# Filter_Board_rev2.net
KiCad netlist of a schematic drawn in EAGLE
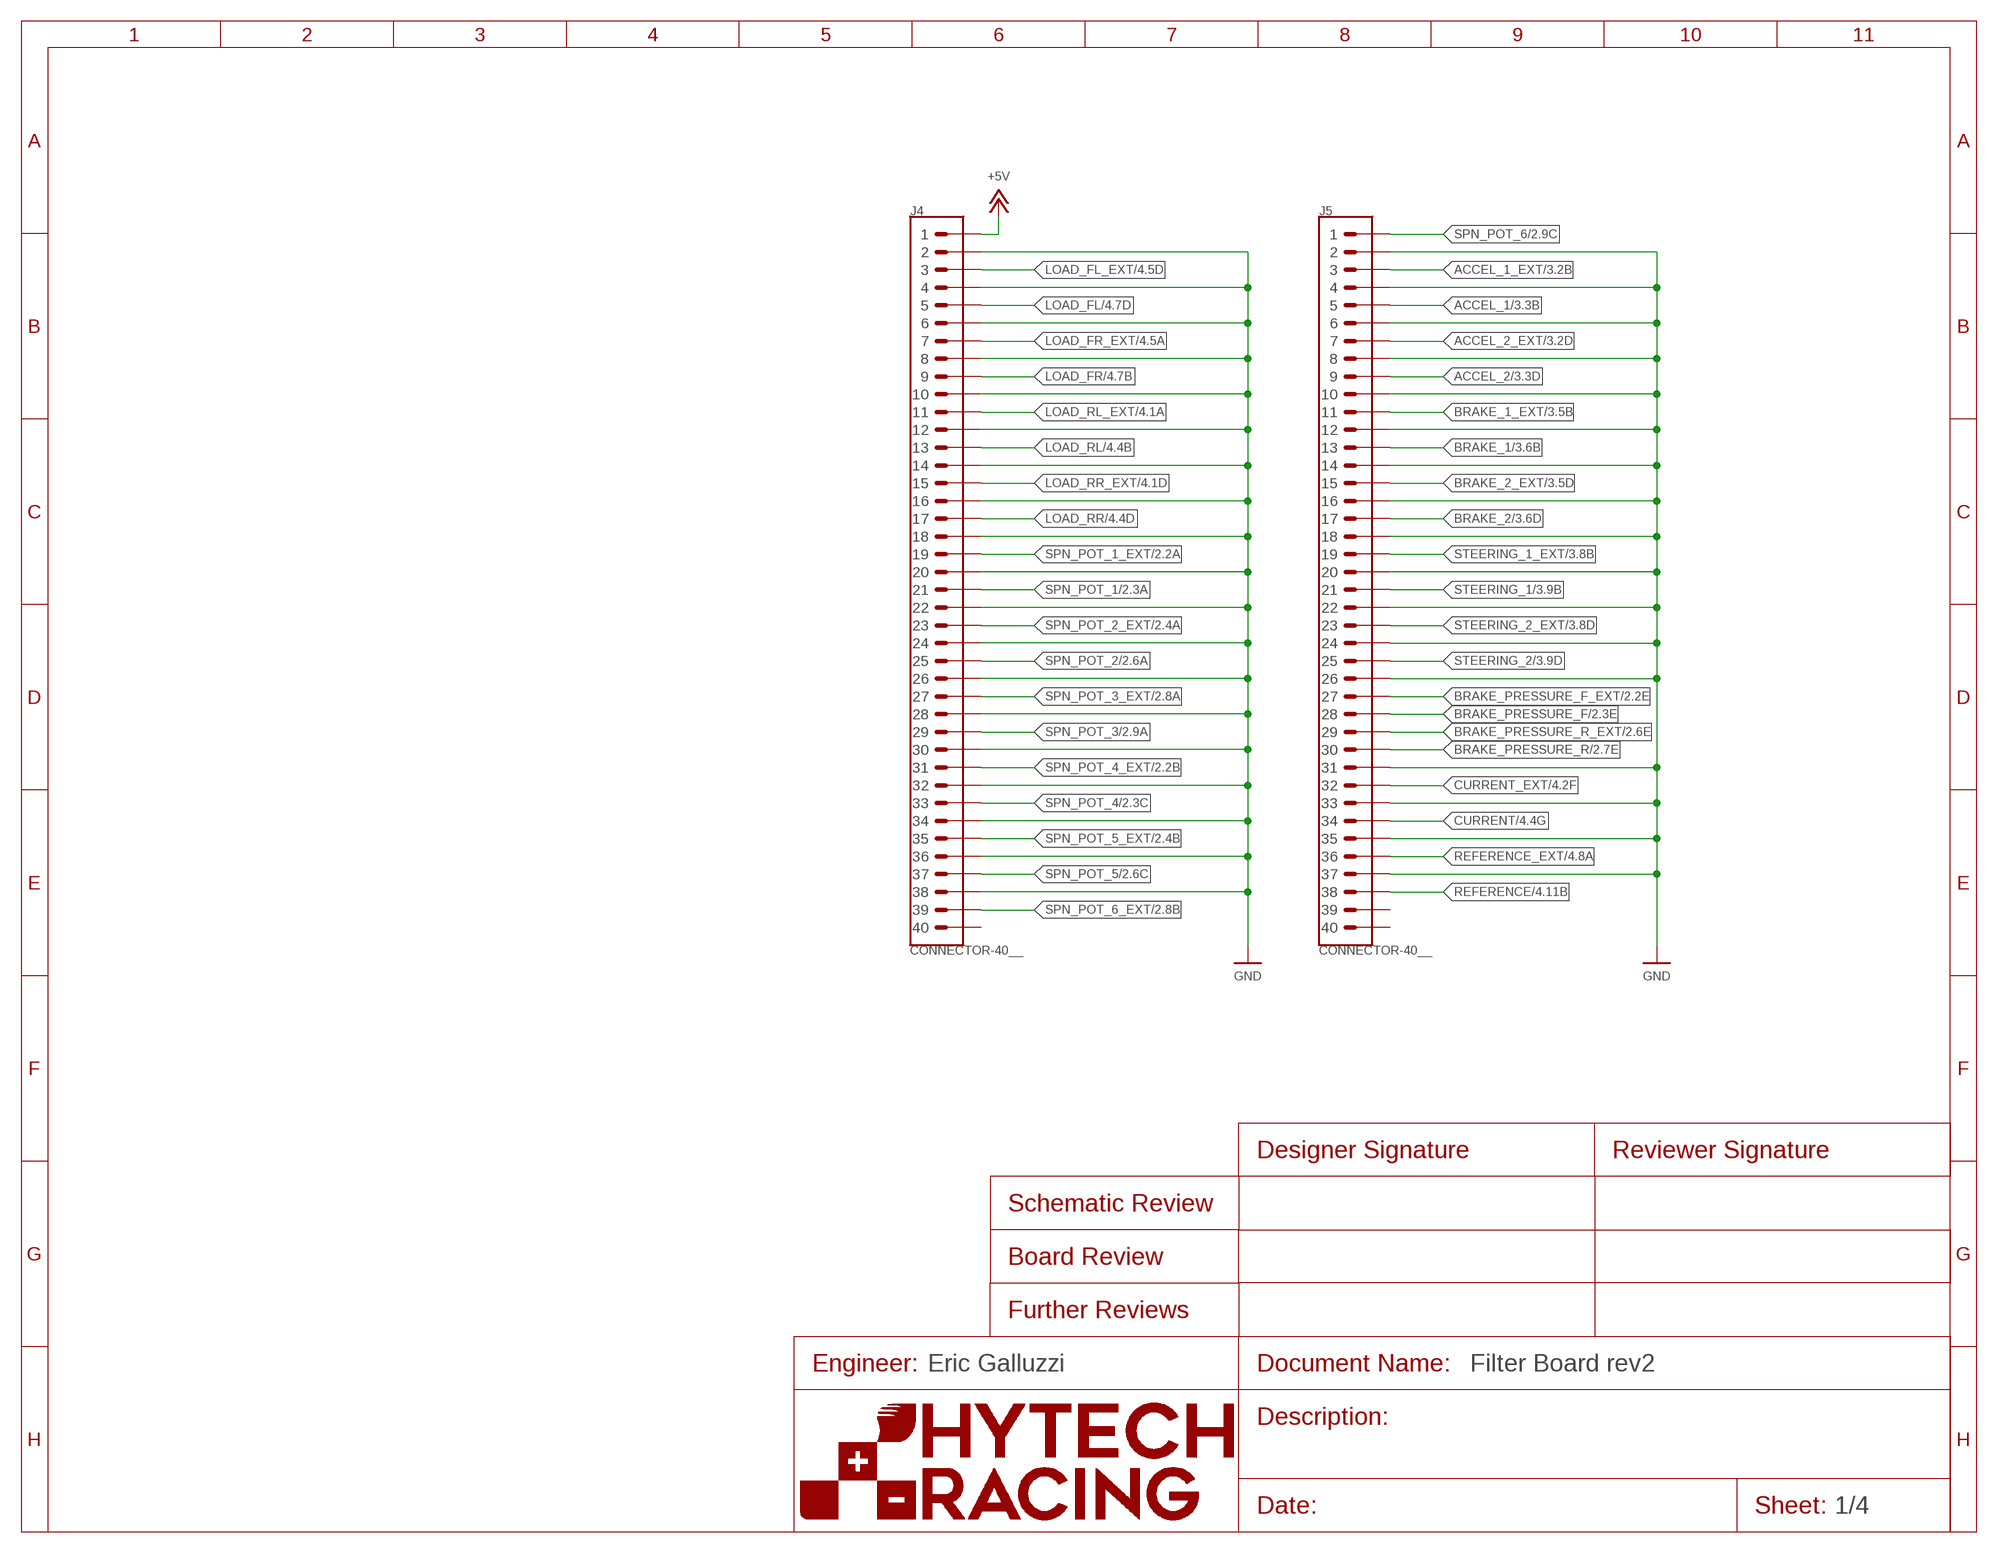
[diagram p0: schematic, sheet 1]
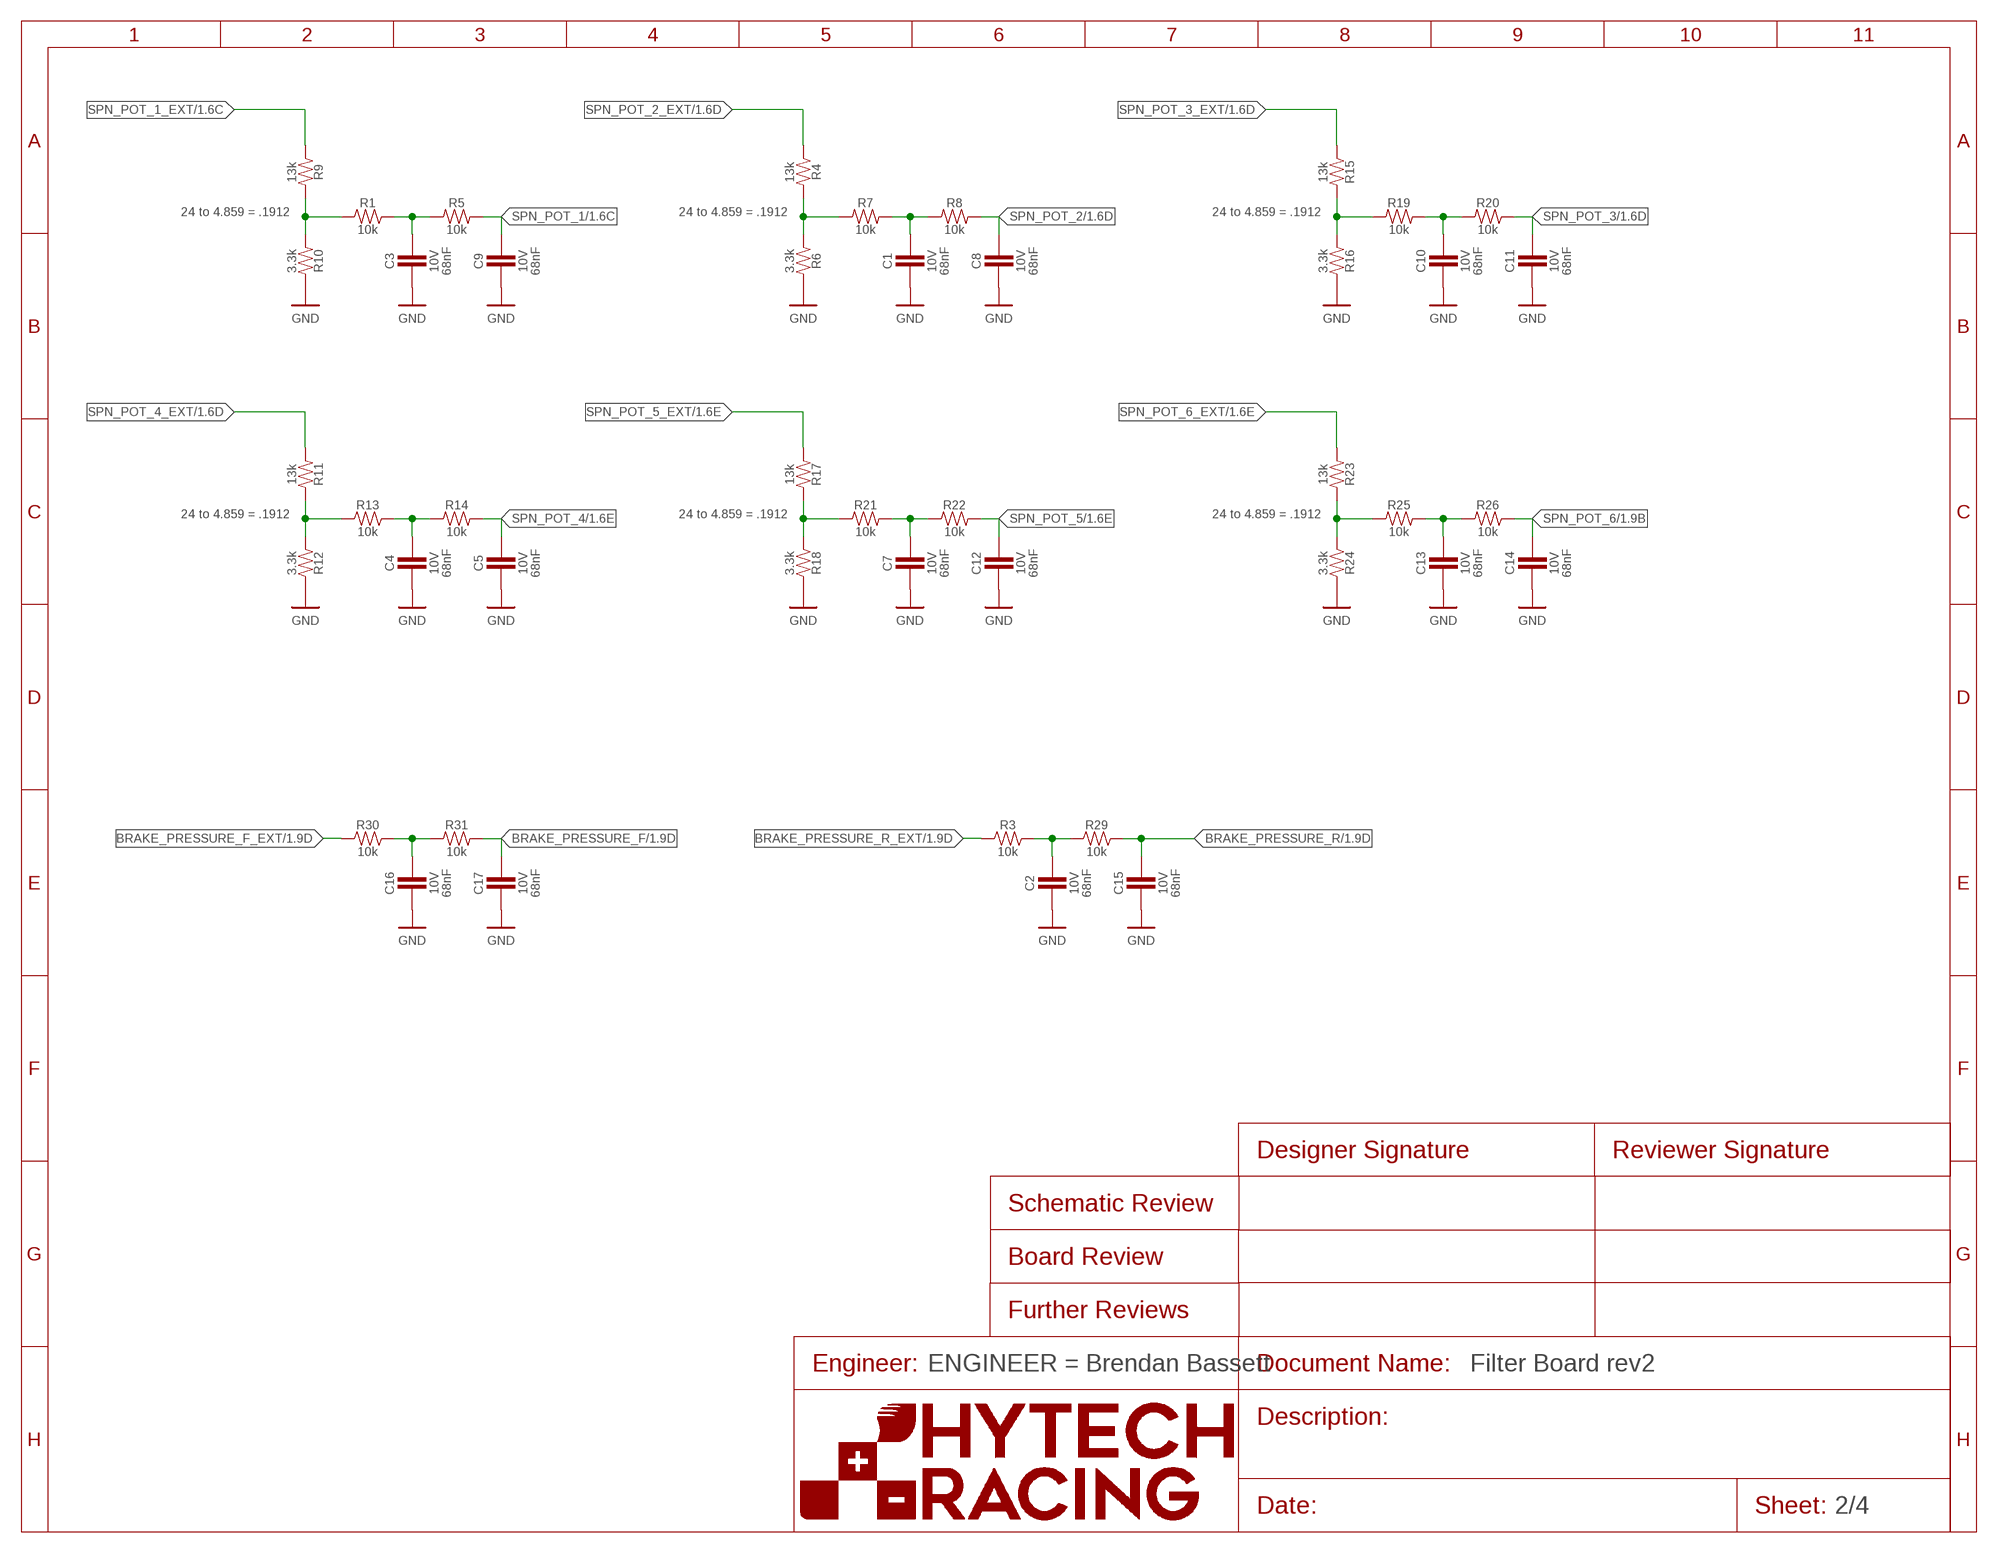
[diagram p1: schematic, sheet 2]
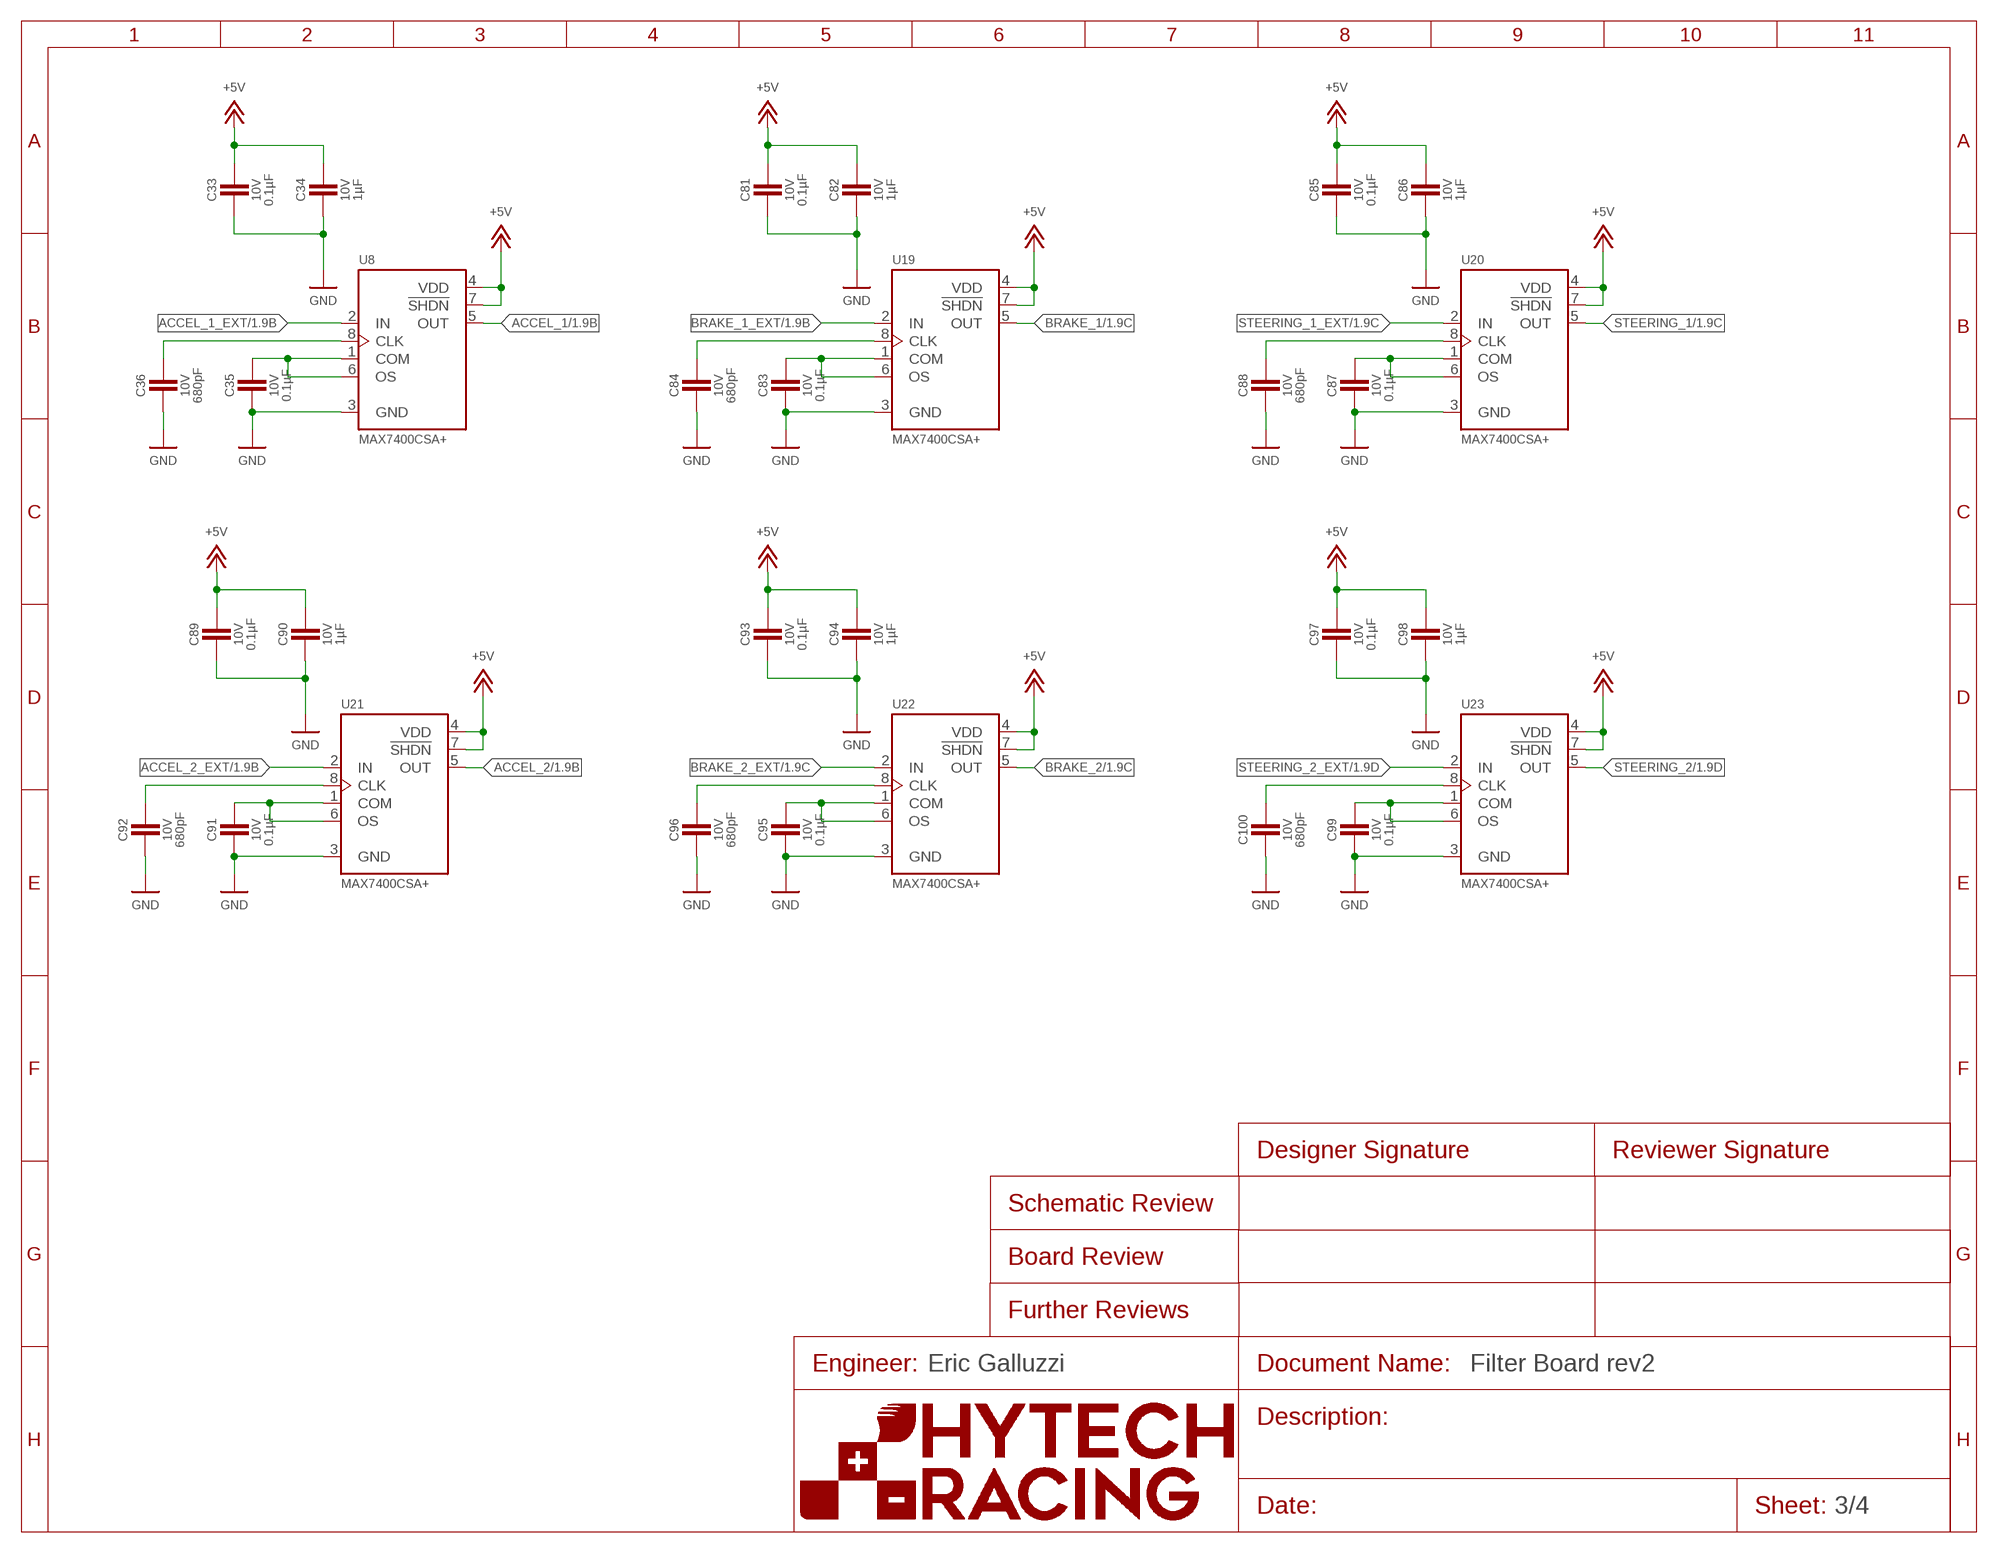
[diagram p2: schematic, sheet 3]
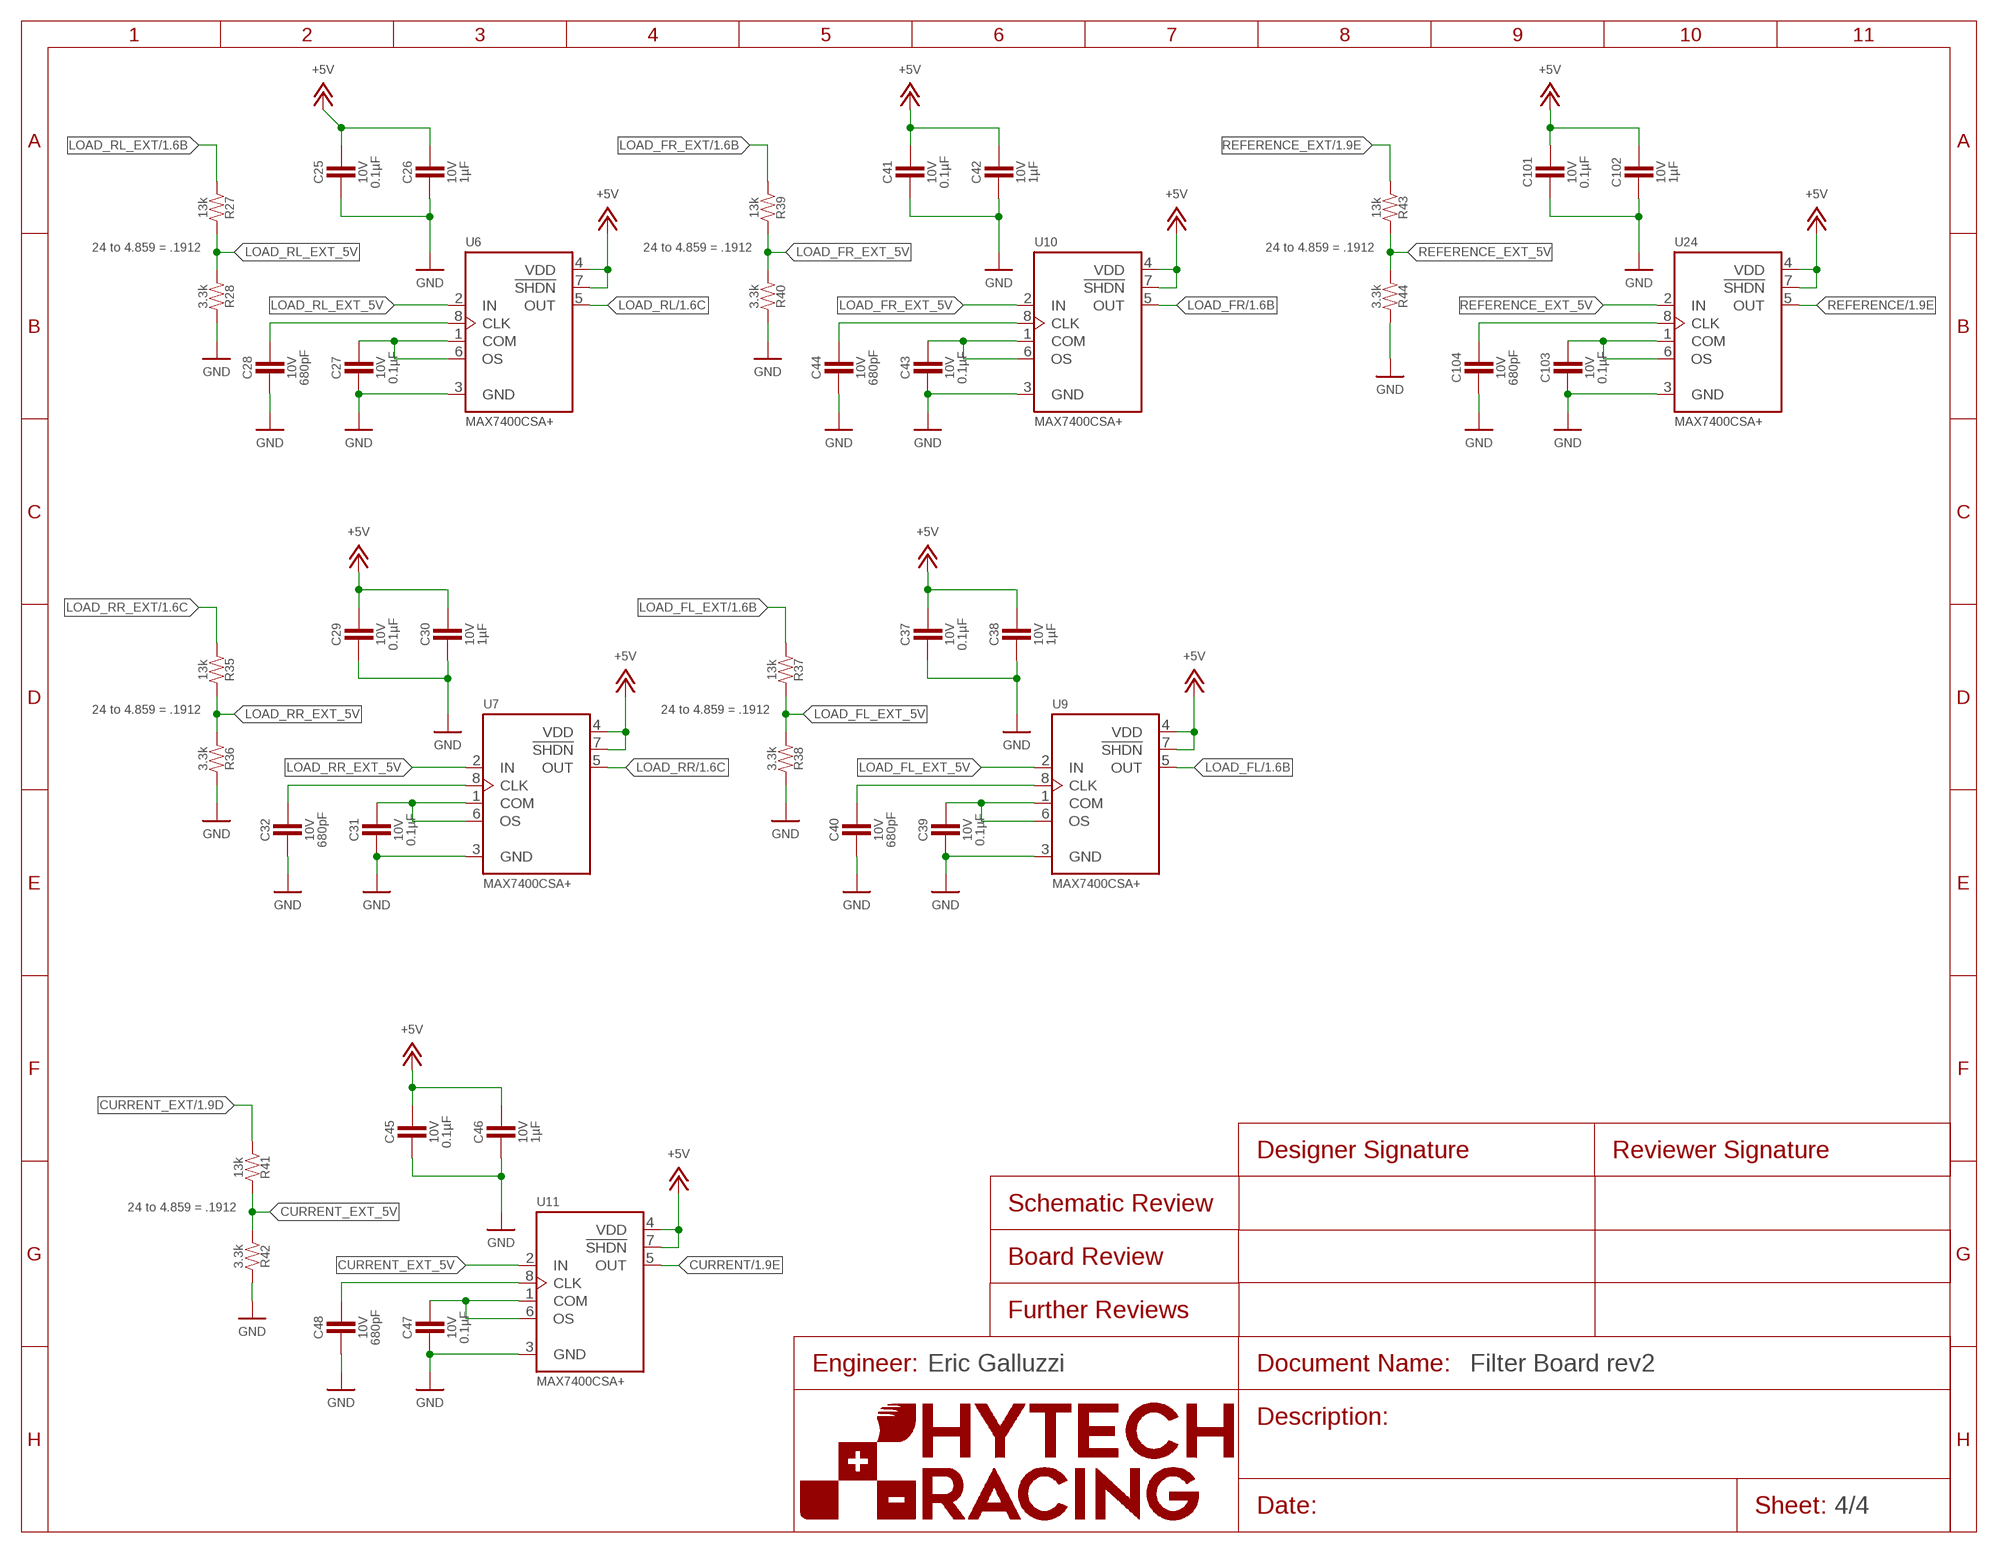
[diagram p3: schematic, sheet 4]

(export (version "E")
  (design (tool "Eeschema 10.0.6"))
  (components
    (comp (ref "C33")
      (value "CAPACITOR_0603_10V_0.1UF")
      (footprint "eagle-import:0603-CAP")
      (fields
        (field (name "CAPACITANCE") "0.1µF")
        (field (name "MANUFACTURER") "Vishay Vitramon")
        (field (name "MPN") "VJ0603Y104JXQPW1BC")
        (field (name "TOLERANCE") "5%")
        (field (name "VOLTAGE") "10V")
      )
      (libsource (lib "eagle-import") (part "CAPACITOR_?_060310V_0.1UF"))
    )
    (comp (ref "C34")
      (value "CAPACITOR_0603_10V_1UF")
      (footprint "eagle-import:0603-CAP")
      (fields
        (field (name "CAPACITANCE") "1µF")
        (field (name "MANUFACTURER") "Yageo")
        (field (name "MPN") "CC0603KRX7R6BB105")
        (field (name "TOLERANCE") "10%")
        (field (name "VOLTAGE") "10V")
      )
      (libsource (lib "eagle-import") (part "CAPACITOR_?_060310V_1UF"))
    )
    (comp (ref "C35")
      (value "CAPACITOR_0603_10V_0.1UF")
      (footprint "eagle-import:0603-CAP")
      (fields
        (field (name "CAPACITANCE") "0.1µF")
        (field (name "MANUFACTURER") "Vishay Vitramon")
        (field (name "MPN") "VJ0603Y104JXQPW1BC")
        (field (name "TOLERANCE") "5%")
        (field (name "VOLTAGE") "10V")
      )
      (libsource (lib "eagle-import") (part "CAPACITOR_?_060310V_0.1UF"))
    )
    (comp (ref "C36")
      (value "CAPACITOR_0603_10V_680PF")
      (footprint "eagle-import:0603-CAP")
      (fields
        (field (name "CAPACITANCE") "680pF")
        (field (name "MANUFACTURER") "Würth Elektronik")
        (field (name "MPN") "885012006013")
        (field (name "TOLERANCE") "5%")
        (field (name "VOLTAGE") "10V")
      )
      (libsource (lib "eagle-import") (part "CAPACITOR_?_060310V_680PF"))
    )
    (comp (ref "C81")
      (value "CAPACITOR_0603_10V_0.1UF")
      (footprint "eagle-import:0603-CAP")
      (fields
        (field (name "CAPACITANCE") "0.1µF")
        (field (name "MANUFACTURER") "Vishay Vitramon")
        (field (name "MPN") "VJ0603Y104JXQPW1BC")
        (field (name "TOLERANCE") "5%")
        (field (name "VOLTAGE") "10V")
      )
      (libsource (lib "eagle-import") (part "CAPACITOR_?_060310V_0.1UF"))
    )
    (comp (ref "C82")
      (value "CAPACITOR_0603_10V_1UF")
      (footprint "eagle-import:0603-CAP")
      (fields
        (field (name "CAPACITANCE") "1µF")
        (field (name "MANUFACTURER") "Yageo")
        (field (name "MPN") "CC0603KRX7R6BB105")
        (field (name "TOLERANCE") "10%")
        (field (name "VOLTAGE") "10V")
      )
      (libsource (lib "eagle-import") (part "CAPACITOR_?_060310V_1UF"))
    )
    (comp (ref "C83")
      (value "CAPACITOR_0603_10V_0.1UF")
      (footprint "eagle-import:0603-CAP")
      (fields
        (field (name "CAPACITANCE") "0.1µF")
        (field (name "MANUFACTURER") "Vishay Vitramon")
        (field (name "MPN") "VJ0603Y104JXQPW1BC")
        (field (name "TOLERANCE") "5%")
        (field (name "VOLTAGE") "10V")
      )
      (libsource (lib "eagle-import") (part "CAPACITOR_?_060310V_0.1UF"))
    )
    (comp (ref "C84")
      (value "CAPACITOR_0603_10V_680PF")
      (footprint "eagle-import:0603-CAP")
      (fields
        (field (name "CAPACITANCE") "680pF")
        (field (name "MANUFACTURER") "Würth Elektronik")
        (field (name "MPN") "885012006013")
        (field (name "TOLERANCE") "5%")
        (field (name "VOLTAGE") "10V")
      )
      (libsource (lib "eagle-import") (part "CAPACITOR_?_060310V_680PF"))
    )
    (comp (ref "C85")
      (value "CAPACITOR_0603_10V_0.1UF")
      (footprint "eagle-import:0603-CAP")
      (fields
        (field (name "CAPACITANCE") "0.1µF")
        (field (name "MANUFACTURER") "Vishay Vitramon")
        (field (name "MPN") "VJ0603Y104JXQPW1BC")
        (field (name "TOLERANCE") "5%")
        (field (name "VOLTAGE") "10V")
      )
      (libsource (lib "eagle-import") (part "CAPACITOR_?_060310V_0.1UF"))
    )
    (comp (ref "C86")
      (value "CAPACITOR_0603_10V_1UF")
      (footprint "eagle-import:0603-CAP")
      (fields
        (field (name "CAPACITANCE") "1µF")
        (field (name "MANUFACTURER") "Yageo")
        (field (name "MPN") "CC0603KRX7R6BB105")
        (field (name "TOLERANCE") "10%")
        (field (name "VOLTAGE") "10V")
      )
      (libsource (lib "eagle-import") (part "CAPACITOR_?_060310V_1UF"))
    )
    (comp (ref "C87")
      (value "CAPACITOR_0603_10V_0.1UF")
      (footprint "eagle-import:0603-CAP")
      (fields
        (field (name "CAPACITANCE") "0.1µF")
        (field (name "MANUFACTURER") "Vishay Vitramon")
        (field (name "MPN") "VJ0603Y104JXQPW1BC")
        (field (name "TOLERANCE") "5%")
        (field (name "VOLTAGE") "10V")
      )
      (libsource (lib "eagle-import") (part "CAPACITOR_?_060310V_0.1UF"))
    )
    (comp (ref "C88")
      (value "CAPACITOR_0603_10V_680PF")
      (footprint "eagle-import:0603-CAP")
      (fields
        (field (name "CAPACITANCE") "680pF")
        (field (name "MANUFACTURER") "Würth Elektronik")
        (field (name "MPN") "885012006013")
        (field (name "TOLERANCE") "5%")
        (field (name "VOLTAGE") "10V")
      )
      (libsource (lib "eagle-import") (part "CAPACITOR_?_060310V_680PF"))
    )
    (comp (ref "C89")
      (value "CAPACITOR_0603_10V_0.1UF")
      (footprint "eagle-import:0603-CAP")
      (fields
        (field (name "CAPACITANCE") "0.1µF")
        (field (name "MANUFACTURER") "Vishay Vitramon")
        (field (name "MPN") "VJ0603Y104JXQPW1BC")
        (field (name "TOLERANCE") "5%")
        (field (name "VOLTAGE") "10V")
      )
      (libsource (lib "eagle-import") (part "CAPACITOR_?_060310V_0.1UF"))
    )
    (comp (ref "C90")
      (value "CAPACITOR_0603_10V_1UF")
      (footprint "eagle-import:0603-CAP")
      (fields
        (field (name "CAPACITANCE") "1µF")
        (field (name "MANUFACTURER") "Yageo")
        (field (name "MPN") "CC0603KRX7R6BB105")
        (field (name "TOLERANCE") "10%")
        (field (name "VOLTAGE") "10V")
      )
      (libsource (lib "eagle-import") (part "CAPACITOR_?_060310V_1UF"))
    )
    (comp (ref "C91")
      (value "CAPACITOR_0603_10V_0.1UF")
      (footprint "eagle-import:0603-CAP")
      (fields
        (field (name "CAPACITANCE") "0.1µF")
        (field (name "MANUFACTURER") "Vishay Vitramon")
        (field (name "MPN") "VJ0603Y104JXQPW1BC")
        (field (name "TOLERANCE") "5%")
        (field (name "VOLTAGE") "10V")
      )
      (libsource (lib "eagle-import") (part "CAPACITOR_?_060310V_0.1UF"))
    )
    (comp (ref "C92")
      (value "CAPACITOR_0603_10V_680PF")
      (footprint "eagle-import:0603-CAP")
      (fields
        (field (name "CAPACITANCE") "680pF")
        (field (name "MANUFACTURER") "Würth Elektronik")
        (field (name "MPN") "885012006013")
        (field (name "TOLERANCE") "5%")
        (field (name "VOLTAGE") "10V")
      )
      (libsource (lib "eagle-import") (part "CAPACITOR_?_060310V_680PF"))
    )
    (comp (ref "C93")
      (value "CAPACITOR_0603_10V_0.1UF")
      (footprint "eagle-import:0603-CAP")
      (fields
        (field (name "CAPACITANCE") "0.1µF")
        (field (name "MANUFACTURER") "Vishay Vitramon")
        (field (name "MPN") "VJ0603Y104JXQPW1BC")
        (field (name "TOLERANCE") "5%")
        (field (name "VOLTAGE") "10V")
      )
      (libsource (lib "eagle-import") (part "CAPACITOR_?_060310V_0.1UF"))
    )
    (comp (ref "C94")
      (value "CAPACITOR_0603_10V_1UF")
      (footprint "eagle-import:0603-CAP")
      (fields
        (field (name "CAPACITANCE") "1µF")
        (field (name "MANUFACTURER") "Yageo")
        (field (name "MPN") "CC0603KRX7R6BB105")
        (field (name "TOLERANCE") "10%")
        (field (name "VOLTAGE") "10V")
      )
      (libsource (lib "eagle-import") (part "CAPACITOR_?_060310V_1UF"))
    )
    (comp (ref "C95")
      (value "CAPACITOR_0603_10V_0.1UF")
      (footprint "eagle-import:0603-CAP")
      (fields
        (field (name "CAPACITANCE") "0.1µF")
        (field (name "MANUFACTURER") "Vishay Vitramon")
        (field (name "MPN") "VJ0603Y104JXQPW1BC")
        (field (name "TOLERANCE") "5%")
        (field (name "VOLTAGE") "10V")
      )
      (libsource (lib "eagle-import") (part "CAPACITOR_?_060310V_0.1UF"))
    )
    (comp (ref "C96")
      (value "CAPACITOR_0603_10V_680PF")
      (footprint "eagle-import:0603-CAP")
      (fields
        (field (name "CAPACITANCE") "680pF")
        (field (name "MANUFACTURER") "Würth Elektronik")
        (field (name "MPN") "885012006013")
        (field (name "TOLERANCE") "5%")
        (field (name "VOLTAGE") "10V")
      )
      (libsource (lib "eagle-import") (part "CAPACITOR_?_060310V_680PF"))
    )
    (comp (ref "C97")
      (value "CAPACITOR_0603_10V_0.1UF")
      (footprint "eagle-import:0603-CAP")
      (fields
        (field (name "CAPACITANCE") "0.1µF")
        (field (name "MANUFACTURER") "Vishay Vitramon")
        (field (name "MPN") "VJ0603Y104JXQPW1BC")
        (field (name "TOLERANCE") "5%")
        (field (name "VOLTAGE") "10V")
      )
      (libsource (lib "eagle-import") (part "CAPACITOR_?_060310V_0.1UF"))
    )
    (comp (ref "C98")
      (value "CAPACITOR_0603_10V_1UF")
      (footprint "eagle-import:0603-CAP")
      (fields
        (field (name "CAPACITANCE") "1µF")
        (field (name "MANUFACTURER") "Yageo")
        (field (name "MPN") "CC0603KRX7R6BB105")
        (field (name "TOLERANCE") "10%")
        (field (name "VOLTAGE") "10V")
      )
      (libsource (lib "eagle-import") (part "CAPACITOR_?_060310V_1UF"))
    )
    (comp (ref "C99")
      (value "CAPACITOR_0603_10V_0.1UF")
      (footprint "eagle-import:0603-CAP")
      (fields
        (field (name "CAPACITANCE") "0.1µF")
        (field (name "MANUFACTURER") "Vishay Vitramon")
        (field (name "MPN") "VJ0603Y104JXQPW1BC")
        (field (name "TOLERANCE") "5%")
        (field (name "VOLTAGE") "10V")
      )
      (libsource (lib "eagle-import") (part "CAPACITOR_?_060310V_0.1UF"))
    )
    (comp (ref "C100")
      (value "CAPACITOR_0603_10V_680PF")
      (footprint "eagle-import:0603-CAP")
      (fields
        (field (name "CAPACITANCE") "680pF")
        (field (name "MANUFACTURER") "Würth Elektronik")
        (field (name "MPN") "885012006013")
        (field (name "TOLERANCE") "5%")
        (field (name "VOLTAGE") "10V")
      )
      (libsource (lib "eagle-import") (part "CAPACITOR_?_060310V_680PF"))
    )
    (comp (ref "U8")
      (value "MAX7400")
      (footprint "eagle-import:SOIC-08(NARROW,0.15_)")
      (fields (field (name "MANUFACTURER") "Maxim Integrated") (field (name "MPN") "MAX7400CSA+"))
      (libsource (lib "eagle-import") (part "MAX7400"))
    )
    (comp (ref "U19")
      (value "MAX7400")
      (footprint "eagle-import:SOIC-08(NARROW,0.15_)")
      (fields (field (name "MANUFACTURER") "Maxim Integrated") (field (name "MPN") "MAX7400CSA+"))
      (libsource (lib "eagle-import") (part "MAX7400"))
    )
    (comp (ref "U20")
      (value "MAX7400")
      (footprint "eagle-import:SOIC-08(NARROW,0.15_)")
      (fields (field (name "MANUFACTURER") "Maxim Integrated") (field (name "MPN") "MAX7400CSA+"))
      (libsource (lib "eagle-import") (part "MAX7400"))
    )
    (comp (ref "U21")
      (value "MAX7400")
      (footprint "eagle-import:SOIC-08(NARROW,0.15_)")
      (fields (field (name "MANUFACTURER") "Maxim Integrated") (field (name "MPN") "MAX7400CSA+"))
      (libsource (lib "eagle-import") (part "MAX7400"))
    )
    (comp (ref "U22")
      (value "MAX7400")
      (footprint "eagle-import:SOIC-08(NARROW,0.15_)")
      (fields (field (name "MANUFACTURER") "Maxim Integrated") (field (name "MPN") "MAX7400CSA+"))
      (libsource (lib "eagle-import") (part "MAX7400"))
    )
    (comp (ref "U23")
      (value "MAX7400")
      (footprint "eagle-import:SOIC-08(NARROW,0.15_)")
      (fields (field (name "MANUFACTURER") "Maxim Integrated") (field (name "MPN") "MAX7400CSA+"))
      (libsource (lib "eagle-import") (part "MAX7400"))
    )
    (comp (ref "J4")
      (value "CONNECTOR-40__")
      (footprint "eagle-import:EHT-120-01")
      (fields (field (name "MANUFACTURER") "Samtec") (field (name "MPN") "EHT-120-01-S-D"))
      (libsource (lib "eagle-import") (part "CONNECTOR-40_?_"))
    )
    (comp (ref "J5")
      (value "CONNECTOR-40__")
      (footprint "eagle-import:EHT-120-01")
      (fields (field (name "MANUFACTURER") "Samtec") (field (name "MPN") "EHT-120-01-S-D"))
      (libsource (lib "eagle-import") (part "CONNECTOR-40_?_"))
    )
    (comp (ref "C25")
      (value "CAPACITOR_0603_10V_0.1UF")
      (footprint "eagle-import:0603-CAP")
      (fields
        (field (name "CAPACITANCE") "0.1µF")
        (field (name "MANUFACTURER") "Vishay Vitramon")
        (field (name "MPN") "VJ0603Y104JXQPW1BC")
        (field (name "TOLERANCE") "5%")
        (field (name "VOLTAGE") "10V")
      )
      (libsource (lib "eagle-import") (part "CAPACITOR_?_060310V_0.1UF"))
    )
    (comp (ref "C26")
      (value "CAPACITOR_0603_10V_1UF")
      (footprint "eagle-import:0603-CAP")
      (fields
        (field (name "CAPACITANCE") "1µF")
        (field (name "MANUFACTURER") "Yageo")
        (field (name "MPN") "CC0603KRX7R6BB105")
        (field (name "TOLERANCE") "10%")
        (field (name "VOLTAGE") "10V")
      )
      (libsource (lib "eagle-import") (part "CAPACITOR_?_060310V_1UF"))
    )
    (comp (ref "C27")
      (value "CAPACITOR_0603_10V_0.1UF")
      (footprint "eagle-import:0603-CAP")
      (fields
        (field (name "CAPACITANCE") "0.1µF")
        (field (name "MANUFACTURER") "Vishay Vitramon")
        (field (name "MPN") "VJ0603Y104JXQPW1BC")
        (field (name "TOLERANCE") "5%")
        (field (name "VOLTAGE") "10V")
      )
      (libsource (lib "eagle-import") (part "CAPACITOR_?_060310V_0.1UF"))
    )
    (comp (ref "C28")
      (value "CAPACITOR_0603_10V_680PF")
      (footprint "eagle-import:0603-CAP")
      (fields
        (field (name "CAPACITANCE") "680pF")
        (field (name "MANUFACTURER") "Würth Elektronik")
        (field (name "MPN") "885012006013")
        (field (name "TOLERANCE") "5%")
        (field (name "VOLTAGE") "10V")
      )
      (libsource (lib "eagle-import") (part "CAPACITOR_?_060310V_680PF"))
    )
    (comp (ref "C29")
      (value "CAPACITOR_0603_10V_0.1UF")
      (footprint "eagle-import:0603-CAP")
      (fields
        (field (name "CAPACITANCE") "0.1µF")
        (field (name "MANUFACTURER") "Vishay Vitramon")
        (field (name "MPN") "VJ0603Y104JXQPW1BC")
        (field (name "TOLERANCE") "5%")
        (field (name "VOLTAGE") "10V")
      )
      (libsource (lib "eagle-import") (part "CAPACITOR_?_060310V_0.1UF"))
    )
    (comp (ref "C30")
      (value "CAPACITOR_0603_10V_1UF")
      (footprint "eagle-import:0603-CAP")
      (fields
        (field (name "CAPACITANCE") "1µF")
        (field (name "MANUFACTURER") "Yageo")
        (field (name "MPN") "CC0603KRX7R6BB105")
        (field (name "TOLERANCE") "10%")
        (field (name "VOLTAGE") "10V")
      )
      (libsource (lib "eagle-import") (part "CAPACITOR_?_060310V_1UF"))
    )
    (comp (ref "C31")
      (value "CAPACITOR_0603_10V_0.1UF")
      (footprint "eagle-import:0603-CAP")
      (fields
        (field (name "CAPACITANCE") "0.1µF")
        (field (name "MANUFACTURER") "Vishay Vitramon")
        (field (name "MPN") "VJ0603Y104JXQPW1BC")
        (field (name "TOLERANCE") "5%")
        (field (name "VOLTAGE") "10V")
      )
      (libsource (lib "eagle-import") (part "CAPACITOR_?_060310V_0.1UF"))
    )
    (comp (ref "C32")
      (value "CAPACITOR_0603_10V_680PF")
      (footprint "eagle-import:0603-CAP")
      (fields
        (field (name "CAPACITANCE") "680pF")
        (field (name "MANUFACTURER") "Würth Elektronik")
        (field (name "MPN") "885012006013")
        (field (name "TOLERANCE") "5%")
        (field (name "VOLTAGE") "10V")
      )
      (libsource (lib "eagle-import") (part "CAPACITOR_?_060310V_680PF"))
    )
    (comp (ref "C37")
      (value "CAPACITOR_0603_10V_0.1UF")
      (footprint "eagle-import:0603-CAP")
      (fields
        (field (name "CAPACITANCE") "0.1µF")
        (field (name "MANUFACTURER") "Vishay Vitramon")
        (field (name "MPN") "VJ0603Y104JXQPW1BC")
        (field (name "TOLERANCE") "5%")
        (field (name "VOLTAGE") "10V")
      )
      (libsource (lib "eagle-import") (part "CAPACITOR_?_060310V_0.1UF"))
    )
    (comp (ref "C38")
      (value "CAPACITOR_0603_10V_1UF")
      (footprint "eagle-import:0603-CAP")
      (fields
        (field (name "CAPACITANCE") "1µF")
        (field (name "MANUFACTURER") "Yageo")
        (field (name "MPN") "CC0603KRX7R6BB105")
        (field (name "TOLERANCE") "10%")
        (field (name "VOLTAGE") "10V")
      )
      (libsource (lib "eagle-import") (part "CAPACITOR_?_060310V_1UF"))
    )
    (comp (ref "C39")
      (value "CAPACITOR_0603_10V_0.1UF")
      (footprint "eagle-import:0603-CAP")
      (fields
        (field (name "CAPACITANCE") "0.1µF")
        (field (name "MANUFACTURER") "Vishay Vitramon")
        (field (name "MPN") "VJ0603Y104JXQPW1BC")
        (field (name "TOLERANCE") "5%")
        (field (name "VOLTAGE") "10V")
      )
      (libsource (lib "eagle-import") (part "CAPACITOR_?_060310V_0.1UF"))
    )
    (comp (ref "C40")
      (value "CAPACITOR_0603_10V_680PF")
      (footprint "eagle-import:0603-CAP")
      (fields
        (field (name "CAPACITANCE") "680pF")
        (field (name "MANUFACTURER") "Würth Elektronik")
        (field (name "MPN") "885012006013")
        (field (name "TOLERANCE") "5%")
        (field (name "VOLTAGE") "10V")
      )
      (libsource (lib "eagle-import") (part "CAPACITOR_?_060310V_680PF"))
    )
    (comp (ref "C41")
      (value "CAPACITOR_0603_10V_0.1UF")
      (footprint "eagle-import:0603-CAP")
      (fields
        (field (name "CAPACITANCE") "0.1µF")
        (field (name "MANUFACTURER") "Vishay Vitramon")
        (field (name "MPN") "VJ0603Y104JXQPW1BC")
        (field (name "TOLERANCE") "5%")
        (field (name "VOLTAGE") "10V")
      )
      (libsource (lib "eagle-import") (part "CAPACITOR_?_060310V_0.1UF"))
    )
    (comp (ref "C42")
      (value "CAPACITOR_0603_10V_1UF")
      (footprint "eagle-import:0603-CAP")
      (fields
        (field (name "CAPACITANCE") "1µF")
        (field (name "MANUFACTURER") "Yageo")
        (field (name "MPN") "CC0603KRX7R6BB105")
        (field (name "TOLERANCE") "10%")
        (field (name "VOLTAGE") "10V")
      )
      (libsource (lib "eagle-import") (part "CAPACITOR_?_060310V_1UF"))
    )
    (comp (ref "C43")
      (value "CAPACITOR_0603_10V_0.1UF")
      (footprint "eagle-import:0603-CAP")
      (fields
        (field (name "CAPACITANCE") "0.1µF")
        (field (name "MANUFACTURER") "Vishay Vitramon")
        (field (name "MPN") "VJ0603Y104JXQPW1BC")
        (field (name "TOLERANCE") "5%")
        (field (name "VOLTAGE") "10V")
      )
      (libsource (lib "eagle-import") (part "CAPACITOR_?_060310V_0.1UF"))
    )
    (comp (ref "C44")
      (value "CAPACITOR_0603_10V_680PF")
      (footprint "eagle-import:0603-CAP")
      (fields
        (field (name "CAPACITANCE") "680pF")
        (field (name "MANUFACTURER") "Würth Elektronik")
        (field (name "MPN") "885012006013")
        (field (name "TOLERANCE") "5%")
        (field (name "VOLTAGE") "10V")
      )
      (libsource (lib "eagle-import") (part "CAPACITOR_?_060310V_680PF"))
    )
    (comp (ref "C45")
      (value "CAPACITOR_0603_10V_0.1UF")
      (footprint "eagle-import:0603-CAP")
      (fields
        (field (name "CAPACITANCE") "0.1µF")
        (field (name "MANUFACTURER") "Vishay Vitramon")
        (field (name "MPN") "VJ0603Y104JXQPW1BC")
        (field (name "TOLERANCE") "5%")
        (field (name "VOLTAGE") "10V")
      )
      (libsource (lib "eagle-import") (part "CAPACITOR_?_060310V_0.1UF"))
    )
    (comp (ref "C46")
      (value "CAPACITOR_0603_10V_1UF")
      (footprint "eagle-import:0603-CAP")
      (fields
        (field (name "CAPACITANCE") "1µF")
        (field (name "MANUFACTURER") "Yageo")
        (field (name "MPN") "CC0603KRX7R6BB105")
        (field (name "TOLERANCE") "10%")
        (field (name "VOLTAGE") "10V")
      )
      (libsource (lib "eagle-import") (part "CAPACITOR_?_060310V_1UF"))
    )
    (comp (ref "C47")
      (value "CAPACITOR_0603_10V_0.1UF")
      (footprint "eagle-import:0603-CAP")
      (fields
        (field (name "CAPACITANCE") "0.1µF")
        (field (name "MANUFACTURER") "Vishay Vitramon")
        (field (name "MPN") "VJ0603Y104JXQPW1BC")
        (field (name "TOLERANCE") "5%")
        (field (name "VOLTAGE") "10V")
      )
      (libsource (lib "eagle-import") (part "CAPACITOR_?_060310V_0.1UF"))
    )
    (comp (ref "C48")
      (value "CAPACITOR_0603_10V_680PF")
      (footprint "eagle-import:0603-CAP")
      (fields
        (field (name "CAPACITANCE") "680pF")
        (field (name "MANUFACTURER") "Würth Elektronik")
        (field (name "MPN") "885012006013")
        (field (name "TOLERANCE") "5%")
        (field (name "VOLTAGE") "10V")
      )
      (libsource (lib "eagle-import") (part "CAPACITOR_?_060310V_680PF"))
    )
    (comp (ref "C101")
      (value "CAPACITOR_0603_10V_0.1UF")
      (footprint "eagle-import:0603-CAP")
      (fields
        (field (name "CAPACITANCE") "0.1µF")
        (field (name "MANUFACTURER") "Vishay Vitramon")
        (field (name "MPN") "VJ0603Y104JXQPW1BC")
        (field (name "TOLERANCE") "5%")
        (field (name "VOLTAGE") "10V")
      )
      (libsource (lib "eagle-import") (part "CAPACITOR_?_060310V_0.1UF"))
    )
    (comp (ref "C102")
      (value "CAPACITOR_0603_10V_1UF")
      (footprint "eagle-import:0603-CAP")
      (fields
        (field (name "CAPACITANCE") "1µF")
        (field (name "MANUFACTURER") "Yageo")
        (field (name "MPN") "CC0603KRX7R6BB105")
        (field (name "TOLERANCE") "10%")
        (field (name "VOLTAGE") "10V")
      )
      (libsource (lib "eagle-import") (part "CAPACITOR_?_060310V_1UF"))
    )
    (comp (ref "C103")
      (value "CAPACITOR_0603_10V_0.1UF")
      (footprint "eagle-import:0603-CAP")
      (fields
        (field (name "CAPACITANCE") "0.1µF")
        (field (name "MANUFACTURER") "Vishay Vitramon")
        (field (name "MPN") "VJ0603Y104JXQPW1BC")
        (field (name "TOLERANCE") "5%")
        (field (name "VOLTAGE") "10V")
      )
      (libsource (lib "eagle-import") (part "CAPACITOR_?_060310V_0.1UF"))
    )
    (comp (ref "C104")
      (value "CAPACITOR_0603_10V_680PF")
      (footprint "eagle-import:0603-CAP")
      (fields
        (field (name "CAPACITANCE") "680pF")
        (field (name "MANUFACTURER") "Würth Elektronik")
        (field (name "MPN") "885012006013")
        (field (name "TOLERANCE") "5%")
        (field (name "VOLTAGE") "10V")
      )
      (libsource (lib "eagle-import") (part "CAPACITOR_?_060310V_680PF"))
    )
    (comp (ref "R27")
      (value "RESISTOR_0603_13K")
      (footprint "eagle-import:0603-RES")
      (fields
        (field (name "MANUFACTURER") "Panasonic Electronic Components")
        (field (name "MPN") "ERA-3ARW133V")
        (field (name "POWER") "0.1W")
        (field (name "RESISTANCE") "13k")
      )
      (libsource (lib "eagle-import") (part "RESISTOR_?_060313K"))
    )
    (comp (ref "R28")
      (value "RESISTOR_0603_3.3K")
      (footprint "eagle-import:0603-RES")
      (fields
        (field (name "MANUFACTURER") "Panasonic Electronic Components")
        (field (name "MPN") "ERJ-PB3D3301V")
        (field (name "POWER") "0.2W")
        (field (name "RESISTANCE") "3.3k")
      )
      (libsource (lib "eagle-import") (part "RESISTOR_?_06033.3K"))
    )
    (comp (ref "R35")
      (value "RESISTOR_0603_13K")
      (footprint "eagle-import:0603-RES")
      (fields
        (field (name "MANUFACTURER") "Panasonic Electronic Components")
        (field (name "MPN") "ERA-3ARW133V")
        (field (name "POWER") "0.1W")
        (field (name "RESISTANCE") "13k")
      )
      (libsource (lib "eagle-import") (part "RESISTOR_?_060313K"))
    )
    (comp (ref "R36")
      (value "RESISTOR_0603_3.3K")
      (footprint "eagle-import:0603-RES")
      (fields
        (field (name "MANUFACTURER") "Panasonic Electronic Components")
        (field (name "MPN") "ERJ-PB3D3301V")
        (field (name "POWER") "0.2W")
        (field (name "RESISTANCE") "3.3k")
      )
      (libsource (lib "eagle-import") (part "RESISTOR_?_06033.3K"))
    )
    (comp (ref "R37")
      (value "RESISTOR_0603_13K")
      (footprint "eagle-import:0603-RES")
      (fields
        (field (name "MANUFACTURER") "Panasonic Electronic Components")
        (field (name "MPN") "ERA-3ARW133V")
        (field (name "POWER") "0.1W")
        (field (name "RESISTANCE") "13k")
      )
      (libsource (lib "eagle-import") (part "RESISTOR_?_060313K"))
    )
    (comp (ref "R38")
      (value "RESISTOR_0603_3.3K")
      (footprint "eagle-import:0603-RES")
      (fields
        (field (name "MANUFACTURER") "Panasonic Electronic Components")
        (field (name "MPN") "ERJ-PB3D3301V")
        (field (name "POWER") "0.2W")
        (field (name "RESISTANCE") "3.3k")
      )
      (libsource (lib "eagle-import") (part "RESISTOR_?_06033.3K"))
    )
    (comp (ref "R39")
      (value "RESISTOR_0603_13K")
      (footprint "eagle-import:0603-RES")
      (fields
        (field (name "MANUFACTURER") "Panasonic Electronic Components")
        (field (name "MPN") "ERA-3ARW133V")
        (field (name "POWER") "0.1W")
        (field (name "RESISTANCE") "13k")
      )
      (libsource (lib "eagle-import") (part "RESISTOR_?_060313K"))
    )
    (comp (ref "R40")
      (value "RESISTOR_0603_3.3K")
      (footprint "eagle-import:0603-RES")
      (fields
        (field (name "MANUFACTURER") "Panasonic Electronic Components")
        (field (name "MPN") "ERJ-PB3D3301V")
        (field (name "POWER") "0.2W")
        (field (name "RESISTANCE") "3.3k")
      )
      (libsource (lib "eagle-import") (part "RESISTOR_?_06033.3K"))
    )
    (comp (ref "R41")
      (value "RESISTOR_0603_13K")
      (footprint "eagle-import:0603-RES")
      (fields
        (field (name "MANUFACTURER") "Panasonic Electronic Components")
        (field (name "MPN") "ERA-3ARW133V")
        (field (name "POWER") "0.1W")
        (field (name "RESISTANCE") "13k")
      )
      (libsource (lib "eagle-import") (part "RESISTOR_?_060313K"))
    )
    (comp (ref "R42")
      (value "RESISTOR_0603_3.3K")
      (footprint "eagle-import:0603-RES")
      (fields
        (field (name "MANUFACTURER") "Panasonic Electronic Components")
        (field (name "MPN") "ERJ-PB3D3301V")
        (field (name "POWER") "0.2W")
        (field (name "RESISTANCE") "3.3k")
      )
      (libsource (lib "eagle-import") (part "RESISTOR_?_06033.3K"))
    )
    (comp (ref "R43")
      (value "RESISTOR_0603_13K")
      (footprint "eagle-import:0603-RES")
      (fields
        (field (name "MANUFACTURER") "Panasonic Electronic Components")
        (field (name "MPN") "ERA-3ARW133V")
        (field (name "POWER") "0.1W")
        (field (name "RESISTANCE") "13k")
      )
      (libsource (lib "eagle-import") (part "RESISTOR_?_060313K"))
    )
    (comp (ref "R44")
      (value "RESISTOR_0603_3.3K")
      (footprint "eagle-import:0603-RES")
      (fields
        (field (name "MANUFACTURER") "Panasonic Electronic Components")
        (field (name "MPN") "ERJ-PB3D3301V")
        (field (name "POWER") "0.2W")
        (field (name "RESISTANCE") "3.3k")
      )
      (libsource (lib "eagle-import") (part "RESISTOR_?_06033.3K"))
    )
    (comp (ref "U6")
      (value "MAX7400")
      (footprint "eagle-import:SOIC-08(NARROW,0.15_)")
      (fields (field (name "MANUFACTURER") "Maxim Integrated") (field (name "MPN") "MAX7400CSA+"))
      (libsource (lib "eagle-import") (part "MAX7400"))
    )
    (comp (ref "U7")
      (value "MAX7400")
      (footprint "eagle-import:SOIC-08(NARROW,0.15_)")
      (fields (field (name "MANUFACTURER") "Maxim Integrated") (field (name "MPN") "MAX7400CSA+"))
      (libsource (lib "eagle-import") (part "MAX7400"))
    )
    (comp (ref "U9")
      (value "MAX7400")
      (footprint "eagle-import:SOIC-08(NARROW,0.15_)")
      (fields (field (name "MANUFACTURER") "Maxim Integrated") (field (name "MPN") "MAX7400CSA+"))
      (libsource (lib "eagle-import") (part "MAX7400"))
    )
    (comp (ref "U10")
      (value "MAX7400")
      (footprint "eagle-import:SOIC-08(NARROW,0.15_)")
      (fields (field (name "MANUFACTURER") "Maxim Integrated") (field (name "MPN") "MAX7400CSA+"))
      (libsource (lib "eagle-import") (part "MAX7400"))
    )
    (comp (ref "U11")
      (value "MAX7400")
      (footprint "eagle-import:SOIC-08(NARROW,0.15_)")
      (fields (field (name "MANUFACTURER") "Maxim Integrated") (field (name "MPN") "MAX7400CSA+"))
      (libsource (lib "eagle-import") (part "MAX7400"))
    )
    (comp (ref "U24")
      (value "MAX7400")
      (footprint "eagle-import:SOIC-08(NARROW,0.15_)")
      (fields (field (name "MANUFACTURER") "Maxim Integrated") (field (name "MPN") "MAX7400CSA+"))
      (libsource (lib "eagle-import") (part "MAX7400"))
    )
    (comp (ref "C1")
      (value "CAPACITOR_0603_10V_68NF")
      (footprint "eagle-import:0603-CAP")
      (fields
        (field (name "CAPACITANCE") "68nF")
        (field (name "MANUFACTURER") "KEMET")
        (field (name "MPN") "C0603C683K8RACTU")
        (field (name "TOLERANCE") "10%")
        (field (name "VOLTAGE") "10V")
      )
      (libsource (lib "eagle-import") (part "CAPACITOR_?_060310V_68NF"))
    )
    (comp (ref "C2")
      (value "CAPACITOR_0603_10V_68NF")
      (footprint "eagle-import:0603-CAP")
      (fields
        (field (name "CAPACITANCE") "68nF")
        (field (name "MANUFACTURER") "KEMET")
        (field (name "MPN") "C0603C683K8RACTU")
        (field (name "TOLERANCE") "10%")
        (field (name "VOLTAGE") "10V")
      )
      (libsource (lib "eagle-import") (part "CAPACITOR_?_060310V_68NF"))
    )
    (comp (ref "C3")
      (value "CAPACITOR_0603_10V_68NF")
      (footprint "eagle-import:0603-CAP")
      (fields
        (field (name "CAPACITANCE") "68nF")
        (field (name "MANUFACTURER") "KEMET")
        (field (name "MPN") "C0603C683K8RACTU")
        (field (name "TOLERANCE") "10%")
        (field (name "VOLTAGE") "10V")
      )
      (libsource (lib "eagle-import") (part "CAPACITOR_?_060310V_68NF"))
    )
    (comp (ref "C4")
      (value "CAPACITOR_0603_10V_68NF")
      (footprint "eagle-import:0603-CAP")
      (fields
        (field (name "CAPACITANCE") "68nF")
        (field (name "MANUFACTURER") "KEMET")
        (field (name "MPN") "C0603C683K8RACTU")
        (field (name "TOLERANCE") "10%")
        (field (name "VOLTAGE") "10V")
      )
      (libsource (lib "eagle-import") (part "CAPACITOR_?_060310V_68NF"))
    )
    (comp (ref "C5")
      (value "CAPACITOR_0603_10V_68NF")
      (footprint "eagle-import:0603-CAP")
      (fields
        (field (name "CAPACITANCE") "68nF")
        (field (name "MANUFACTURER") "KEMET")
        (field (name "MPN") "C0603C683K8RACTU")
        (field (name "TOLERANCE") "10%")
        (field (name "VOLTAGE") "10V")
      )
      (libsource (lib "eagle-import") (part "CAPACITOR_?_060310V_68NF"))
    )
    (comp (ref "C7")
      (value "CAPACITOR_0603_10V_68NF")
      (footprint "eagle-import:0603-CAP")
      (fields
        (field (name "CAPACITANCE") "68nF")
        (field (name "MANUFACTURER") "KEMET")
        (field (name "MPN") "C0603C683K8RACTU")
        (field (name "TOLERANCE") "10%")
        (field (name "VOLTAGE") "10V")
      )
      (libsource (lib "eagle-import") (part "CAPACITOR_?_060310V_68NF"))
    )
    (comp (ref "C8")
      (value "CAPACITOR_0603_10V_68NF")
      (footprint "eagle-import:0603-CAP")
      (fields
        (field (name "CAPACITANCE") "68nF")
        (field (name "MANUFACTURER") "KEMET")
        (field (name "MPN") "C0603C683K8RACTU")
        (field (name "TOLERANCE") "10%")
        (field (name "VOLTAGE") "10V")
      )
      (libsource (lib "eagle-import") (part "CAPACITOR_?_060310V_68NF"))
    )
    (comp (ref "C9")
      (value "CAPACITOR_0603_10V_68NF")
      (footprint "eagle-import:0603-CAP")
      (fields
        (field (name "CAPACITANCE") "68nF")
        (field (name "MANUFACTURER") "KEMET")
        (field (name "MPN") "C0603C683K8RACTU")
        (field (name "TOLERANCE") "10%")
        (field (name "VOLTAGE") "10V")
      )
      (libsource (lib "eagle-import") (part "CAPACITOR_?_060310V_68NF"))
    )
    (comp (ref "C10")
      (value "CAPACITOR_0603_10V_68NF")
      (footprint "eagle-import:0603-CAP")
      (fields
        (field (name "CAPACITANCE") "68nF")
        (field (name "MANUFACTURER") "KEMET")
        (field (name "MPN") "C0603C683K8RACTU")
        (field (name "TOLERANCE") "10%")
        (field (name "VOLTAGE") "10V")
      )
      (libsource (lib "eagle-import") (part "CAPACITOR_?_060310V_68NF"))
    )
    (comp (ref "C11")
      (value "CAPACITOR_0603_10V_68NF")
      (footprint "eagle-import:0603-CAP")
      (fields
        (field (name "CAPACITANCE") "68nF")
        (field (name "MANUFACTURER") "KEMET")
        (field (name "MPN") "C0603C683K8RACTU")
        (field (name "TOLERANCE") "10%")
        (field (name "VOLTAGE") "10V")
      )
      (libsource (lib "eagle-import") (part "CAPACITOR_?_060310V_68NF"))
    )
    (comp (ref "C12")
      (value "CAPACITOR_0603_10V_68NF")
      (footprint "eagle-import:0603-CAP")
      (fields
        (field (name "CAPACITANCE") "68nF")
        (field (name "MANUFACTURER") "KEMET")
        (field (name "MPN") "C0603C683K8RACTU")
        (field (name "TOLERANCE") "10%")
        (field (name "VOLTAGE") "10V")
      )
      (libsource (lib "eagle-import") (part "CAPACITOR_?_060310V_68NF"))
    )
    (comp (ref "C13")
      (value "CAPACITOR_0603_10V_68NF")
      (footprint "eagle-import:0603-CAP")
      (fields
        (field (name "CAPACITANCE") "68nF")
        (field (name "MANUFACTURER") "KEMET")
        (field (name "MPN") "C0603C683K8RACTU")
        (field (name "TOLERANCE") "10%")
        (field (name "VOLTAGE") "10V")
      )
      (libsource (lib "eagle-import") (part "CAPACITOR_?_060310V_68NF"))
    )
    (comp (ref "C14")
      (value "CAPACITOR_0603_10V_68NF")
      (footprint "eagle-import:0603-CAP")
      (fields
        (field (name "CAPACITANCE") "68nF")
        (field (name "MANUFACTURER") "KEMET")
        (field (name "MPN") "C0603C683K8RACTU")
        (field (name "TOLERANCE") "10%")
        (field (name "VOLTAGE") "10V")
      )
      (libsource (lib "eagle-import") (part "CAPACITOR_?_060310V_68NF"))
    )
    (comp (ref "C15")
      (value "CAPACITOR_0603_10V_68NF")
      (footprint "eagle-import:0603-CAP")
      (fields
        (field (name "CAPACITANCE") "68nF")
        (field (name "MANUFACTURER") "KEMET")
        (field (name "MPN") "C0603C683K8RACTU")
        (field (name "TOLERANCE") "10%")
        (field (name "VOLTAGE") "10V")
      )
      (libsource (lib "eagle-import") (part "CAPACITOR_?_060310V_68NF"))
    )
    (comp (ref "C16")
      (value "CAPACITOR_0603_10V_68NF")
      (footprint "eagle-import:0603-CAP")
      (fields
        (field (name "CAPACITANCE") "68nF")
        (field (name "MANUFACTURER") "KEMET")
        (field (name "MPN") "C0603C683K8RACTU")
        (field (name "TOLERANCE") "10%")
        (field (name "VOLTAGE") "10V")
      )
      (libsource (lib "eagle-import") (part "CAPACITOR_?_060310V_68NF"))
    )
    (comp (ref "C17")
      (value "CAPACITOR_0603_10V_68NF")
      (footprint "eagle-import:0603-CAP")
      (fields
        (field (name "CAPACITANCE") "68nF")
        (field (name "MANUFACTURER") "KEMET")
        (field (name "MPN") "C0603C683K8RACTU")
        (field (name "TOLERANCE") "10%")
        (field (name "VOLTAGE") "10V")
      )
      (libsource (lib "eagle-import") (part "CAPACITOR_?_060310V_68NF"))
    )
    (comp (ref "R1")
      (value "RESISTOR_0603_10K")
      (footprint "eagle-import:0603-RES")
      (fields
        (field (name "MANUFACTURER") "Yageo")
        (field (name "MPN") "RC0603FR-0710KL")
        (field (name "POWER") "0.1W")
        (field (name "RESISTANCE") "10k")
      )
      (libsource (lib "eagle-import") (part "RESISTOR_?_060310K"))
    )
    (comp (ref "R3")
      (value "RESISTOR_0603_10K")
      (footprint "eagle-import:0603-RES")
      (fields
        (field (name "MANUFACTURER") "Yageo")
        (field (name "MPN") "RC0603FR-0710KL")
        (field (name "POWER") "0.1W")
        (field (name "RESISTANCE") "10k")
      )
      (libsource (lib "eagle-import") (part "RESISTOR_?_060310K"))
    )
    (comp (ref "R4")
      (value "RESISTOR_0603_13K")
      (footprint "eagle-import:0603-RES")
      (fields
        (field (name "MANUFACTURER") "Panasonic Electronic Components")
        (field (name "MPN") "ERA-3ARW133V")
        (field (name "POWER") "0.1W")
        (field (name "RESISTANCE") "13k")
      )
      (libsource (lib "eagle-import") (part "RESISTOR_?_060313K"))
    )
    (comp (ref "R5")
      (value "RESISTOR_0603_10K")
      (footprint "eagle-import:0603-RES")
      (fields
        (field (name "MANUFACTURER") "Yageo")
        (field (name "MPN") "RC0603FR-0710KL")
        (field (name "POWER") "0.1W")
        (field (name "RESISTANCE") "10k")
      )
      (libsource (lib "eagle-import") (part "RESISTOR_?_060310K"))
    )
    (comp (ref "R6")
      (value "RESISTOR_0603_3.3K")
      (footprint "eagle-import:0603-RES")
      (fields
        (field (name "MANUFACTURER") "Panasonic Electronic Components")
        (field (name "MPN") "ERJ-PB3D3301V")
        (field (name "POWER") "0.2W")
        (field (name "RESISTANCE") "3.3k")
      )
      (libsource (lib "eagle-import") (part "RESISTOR_?_06033.3K"))
    )
    (comp (ref "R7")
      (value "RESISTOR_0603_10K")
      (footprint "eagle-import:0603-RES")
      (fields
        (field (name "MANUFACTURER") "Yageo")
        (field (name "MPN") "RC0603FR-0710KL")
        (field (name "POWER") "0.1W")
        (field (name "RESISTANCE") "10k")
      )
      (libsource (lib "eagle-import") (part "RESISTOR_?_060310K"))
    )
    (comp (ref "R8")
      (value "RESISTOR_0603_10K")
      (footprint "eagle-import:0603-RES")
      (fields
        (field (name "MANUFACTURER") "Yageo")
        (field (name "MPN") "RC0603FR-0710KL")
        (field (name "POWER") "0.1W")
        (field (name "RESISTANCE") "10k")
      )
      (libsource (lib "eagle-import") (part "RESISTOR_?_060310K"))
    )
    (comp (ref "R9")
      (value "RESISTOR_0603_13K")
      (footprint "eagle-import:0603-RES")
      (fields
        (field (name "MANUFACTURER") "Panasonic Electronic Components")
        (field (name "MPN") "ERA-3ARW133V")
        (field (name "POWER") "0.1W")
        (field (name "RESISTANCE") "13k")
      )
      (libsource (lib "eagle-import") (part "RESISTOR_?_060313K"))
    )
    (comp (ref "R10")
      (value "RESISTOR_0603_3.3K")
      (footprint "eagle-import:0603-RES")
      (fields
        (field (name "MANUFACTURER") "Panasonic Electronic Components")
        (field (name "MPN") "ERJ-PB3D3301V")
        (field (name "POWER") "0.2W")
        (field (name "RESISTANCE") "3.3k")
      )
      (libsource (lib "eagle-import") (part "RESISTOR_?_06033.3K"))
    )
    (comp (ref "R11")
      (value "RESISTOR_0603_13K")
      (footprint "eagle-import:0603-RES")
      (fields
        (field (name "MANUFACTURER") "Panasonic Electronic Components")
        (field (name "MPN") "ERA-3ARW133V")
        (field (name "POWER") "0.1W")
        (field (name "RESISTANCE") "13k")
      )
      (libsource (lib "eagle-import") (part "RESISTOR_?_060313K"))
    )
    (comp (ref "R12")
      (value "RESISTOR_0603_3.3K")
      (footprint "eagle-import:0603-RES")
      (fields
        (field (name "MANUFACTURER") "Panasonic Electronic Components")
        (field (name "MPN") "ERJ-PB3D3301V")
        (field (name "POWER") "0.2W")
        (field (name "RESISTANCE") "3.3k")
      )
      (libsource (lib "eagle-import") (part "RESISTOR_?_06033.3K"))
    )
    (comp (ref "R13")
      (value "RESISTOR_0603_10K")
      (footprint "eagle-import:0603-RES")
      (fields
        (field (name "MANUFACTURER") "Yageo")
        (field (name "MPN") "RC0603FR-0710KL")
        (field (name "POWER") "0.1W")
        (field (name "RESISTANCE") "10k")
      )
      (libsource (lib "eagle-import") (part "RESISTOR_?_060310K"))
    )
    (comp (ref "R14")
      (value "RESISTOR_0603_10K")
      (footprint "eagle-import:0603-RES")
      (fields
        (field (name "MANUFACTURER") "Yageo")
        (field (name "MPN") "RC0603FR-0710KL")
        (field (name "POWER") "0.1W")
        (field (name "RESISTANCE") "10k")
      )
      (libsource (lib "eagle-import") (part "RESISTOR_?_060310K"))
    )
    (comp (ref "R15")
      (value "RESISTOR_0603_13K")
      (footprint "eagle-import:0603-RES")
      (fields
        (field (name "MANUFACTURER") "Panasonic Electronic Components")
        (field (name "MPN") "ERA-3ARW133V")
        (field (name "POWER") "0.1W")
        (field (name "RESISTANCE") "13k")
      )
      (libsource (lib "eagle-import") (part "RESISTOR_?_060313K"))
    )
    (comp (ref "R16")
      (value "RESISTOR_0603_3.3K")
      (footprint "eagle-import:0603-RES")
      (fields
        (field (name "MANUFACTURER") "Panasonic Electronic Components")
        (field (name "MPN") "ERJ-PB3D3301V")
        (field (name "POWER") "0.2W")
        (field (name "RESISTANCE") "3.3k")
      )
      (libsource (lib "eagle-import") (part "RESISTOR_?_06033.3K"))
    )
    (comp (ref "R17")
      (value "RESISTOR_0603_13K")
      (footprint "eagle-import:0603-RES")
      (fields
        (field (name "MANUFACTURER") "Panasonic Electronic Components")
        (field (name "MPN") "ERA-3ARW133V")
        (field (name "POWER") "0.1W")
        (field (name "RESISTANCE") "13k")
      )
      (libsource (lib "eagle-import") (part "RESISTOR_?_060313K"))
    )
    (comp (ref "R18")
      (value "RESISTOR_0603_3.3K")
      (footprint "eagle-import:0603-RES")
      (fields
        (field (name "MANUFACTURER") "Panasonic Electronic Components")
        (field (name "MPN") "ERJ-PB3D3301V")
        (field (name "POWER") "0.2W")
        (field (name "RESISTANCE") "3.3k")
      )
      (libsource (lib "eagle-import") (part "RESISTOR_?_06033.3K"))
    )
    (comp (ref "R19")
      (value "RESISTOR_0603_10K")
      (footprint "eagle-import:0603-RES")
      (fields
        (field (name "MANUFACTURER") "Yageo")
        (field (name "MPN") "RC0603FR-0710KL")
        (field (name "POWER") "0.1W")
        (field (name "RESISTANCE") "10k")
      )
      (libsource (lib "eagle-import") (part "RESISTOR_?_060310K"))
    )
    (comp (ref "R20")
      (value "RESISTOR_0603_10K")
      (footprint "eagle-import:0603-RES")
      (fields
        (field (name "MANUFACTURER") "Yageo")
        (field (name "MPN") "RC0603FR-0710KL")
        (field (name "POWER") "0.1W")
        (field (name "RESISTANCE") "10k")
      )
      (libsource (lib "eagle-import") (part "RESISTOR_?_060310K"))
    )
    (comp (ref "R21")
      (value "RESISTOR_0603_10K")
      (footprint "eagle-import:0603-RES")
      (fields
        (field (name "MANUFACTURER") "Yageo")
        (field (name "MPN") "RC0603FR-0710KL")
        (field (name "POWER") "0.1W")
        (field (name "RESISTANCE") "10k")
      )
      (libsource (lib "eagle-import") (part "RESISTOR_?_060310K"))
    )
    (comp (ref "R22")
      (value "RESISTOR_0603_10K")
      (footprint "eagle-import:0603-RES")
      (fields
        (field (name "MANUFACTURER") "Yageo")
        (field (name "MPN") "RC0603FR-0710KL")
        (field (name "POWER") "0.1W")
        (field (name "RESISTANCE") "10k")
      )
      (libsource (lib "eagle-import") (part "RESISTOR_?_060310K"))
    )
    (comp (ref "R23")
      (value "RESISTOR_0603_13K")
      (footprint "eagle-import:0603-RES")
      (fields
        (field (name "MANUFACTURER") "Panasonic Electronic Components")
        (field (name "MPN") "ERA-3ARW133V")
        (field (name "POWER") "0.1W")
        (field (name "RESISTANCE") "13k")
      )
      (libsource (lib "eagle-import") (part "RESISTOR_?_060313K"))
    )
    (comp (ref "R24")
      (value "RESISTOR_0603_3.3K")
      (footprint "eagle-import:0603-RES")
      (fields
        (field (name "MANUFACTURER") "Panasonic Electronic Components")
        (field (name "MPN") "ERJ-PB3D3301V")
        (field (name "POWER") "0.2W")
        (field (name "RESISTANCE") "3.3k")
      )
      (libsource (lib "eagle-import") (part "RESISTOR_?_06033.3K"))
    )
    (comp (ref "R25")
      (value "RESISTOR_0603_10K")
      (footprint "eagle-import:0603-RES")
      (fields
        (field (name "MANUFACTURER") "Yageo")
        (field (name "MPN") "RC0603FR-0710KL")
        (field (name "POWER") "0.1W")
        (field (name "RESISTANCE") "10k")
      )
      (libsource (lib "eagle-import") (part "RESISTOR_?_060310K"))
    )
    (comp (ref "R26")
      (value "RESISTOR_0603_10K")
      (footprint "eagle-import:0603-RES")
      (fields
        (field (name "MANUFACTURER") "Yageo")
        (field (name "MPN") "RC0603FR-0710KL")
        (field (name "POWER") "0.1W")
        (field (name "RESISTANCE") "10k")
      )
      (libsource (lib "eagle-import") (part "RESISTOR_?_060310K"))
    )
    (comp (ref "R29")
      (value "RESISTOR_0603_10K")
      (footprint "eagle-import:0603-RES")
      (fields
        (field (name "MANUFACTURER") "Yageo")
        (field (name "MPN") "RC0603FR-0710KL")
        (field (name "POWER") "0.1W")
        (field (name "RESISTANCE") "10k")
      )
      (libsource (lib "eagle-import") (part "RESISTOR_?_060310K"))
    )
    (comp (ref "R30")
      (value "RESISTOR_0603_10K")
      (footprint "eagle-import:0603-RES")
      (fields
        (field (name "MANUFACTURER") "Yageo")
        (field (name "MPN") "RC0603FR-0710KL")
        (field (name "POWER") "0.1W")
        (field (name "RESISTANCE") "10k")
      )
      (libsource (lib "eagle-import") (part "RESISTOR_?_060310K"))
    )
    (comp (ref "R31")
      (value "RESISTOR_0603_10K")
      (footprint "eagle-import:0603-RES")
      (fields
        (field (name "MANUFACTURER") "Yageo")
        (field (name "MPN") "RC0603FR-0710KL")
        (field (name "POWER") "0.1W")
        (field (name "RESISTANCE") "10k")
      )
      (libsource (lib "eagle-import") (part "RESISTOR_?_060310K"))
    )
  )
  (nets
    (net (code "1") (name "+5V") (class "Default")
      (node (ref "C101") (pin "1") (pinfunction "1_1") (pintype "passive"))
      (node (ref "C102") (pin "1") (pinfunction "1_1") (pintype "passive"))
      (node (ref "C25") (pin "1") (pinfunction "1_1") (pintype "passive"))
      (node (ref "C26") (pin "1") (pinfunction "1_1") (pintype "passive"))
      (node (ref "C29") (pin "1") (pinfunction "1_1") (pintype "passive"))
      (node (ref "C30") (pin "1") (pinfunction "1_1") (pintype "passive"))
      (node (ref "C33") (pin "1") (pinfunction "1_1") (pintype "passive"))
      (node (ref "C34") (pin "1") (pinfunction "1_1") (pintype "passive"))
      (node (ref "C37") (pin "1") (pinfunction "1_1") (pintype "passive"))
      (node (ref "C38") (pin "1") (pinfunction "1_1") (pintype "passive"))
      (node (ref "C41") (pin "1") (pinfunction "1_1") (pintype "passive"))
      (node (ref "C42") (pin "1") (pinfunction "1_1") (pintype "passive"))
      (node (ref "C45") (pin "1") (pinfunction "1_1") (pintype "passive"))
      (node (ref "C46") (pin "1") (pinfunction "1_1") (pintype "passive"))
      (node (ref "C81") (pin "1") (pinfunction "1_1") (pintype "passive"))
      (node (ref "C82") (pin "1") (pinfunction "1_1") (pintype "passive"))
      (node (ref "C85") (pin "1") (pinfunction "1_1") (pintype "passive"))
      (node (ref "C86") (pin "1") (pinfunction "1_1") (pintype "passive"))
      (node (ref "C89") (pin "1") (pinfunction "1_1") (pintype "passive"))
      (node (ref "C90") (pin "1") (pinfunction "1_1") (pintype "passive"))
      (node (ref "C93") (pin "1") (pinfunction "1_1") (pintype "passive"))
      (node (ref "C94") (pin "1") (pinfunction "1_1") (pintype "passive"))
      (node (ref "C97") (pin "1") (pinfunction "1_1") (pintype "passive"))
      (node (ref "C98") (pin "1") (pinfunction "1_1") (pintype "passive"))
      (node (ref "J4") (pin "1") (pinfunction "1_1") (pintype "passive"))
      (node (ref "U10") (pin "4") (pinfunction "VDD_4") (pintype "power_in"))
      (node (ref "U10") (pin "7") (pinfunction "~{SHDN}_7") (pintype "input"))
      (node (ref "U11") (pin "4") (pinfunction "VDD_4") (pintype "power_in"))
      (node (ref "U11") (pin "7") (pinfunction "~{SHDN}_7") (pintype "input"))
      (node (ref "U19") (pin "4") (pinfunction "VDD_4") (pintype "power_in"))
      (node (ref "U19") (pin "7") (pinfunction "~{SHDN}_7") (pintype "input"))
      (node (ref "U20") (pin "4") (pinfunction "VDD_4") (pintype "power_in"))
      (node (ref "U20") (pin "7") (pinfunction "~{SHDN}_7") (pintype "input"))
      (node (ref "U21") (pin "4") (pinfunction "VDD_4") (pintype "power_in"))
      (node (ref "U21") (pin "7") (pinfunction "~{SHDN}_7") (pintype "input"))
      (node (ref "U22") (pin "4") (pinfunction "VDD_4") (pintype "power_in"))
      (node (ref "U22") (pin "7") (pinfunction "~{SHDN}_7") (pintype "input"))
      (node (ref "U23") (pin "4") (pinfunction "VDD_4") (pintype "power_in"))
      (node (ref "U23") (pin "7") (pinfunction "~{SHDN}_7") (pintype "input"))
      (node (ref "U24") (pin "4") (pinfunction "VDD_4") (pintype "power_in"))
      (node (ref "U24") (pin "7") (pinfunction "~{SHDN}_7") (pintype "input"))
      (node (ref "U6") (pin "4") (pinfunction "VDD_4") (pintype "power_in"))
      (node (ref "U6") (pin "7") (pinfunction "~{SHDN}_7") (pintype "input"))
      (node (ref "U7") (pin "4") (pinfunction "VDD_4") (pintype "power_in"))
      (node (ref "U7") (pin "7") (pinfunction "~{SHDN}_7") (pintype "input"))
      (node (ref "U8") (pin "4") (pinfunction "VDD_4") (pintype "power_in"))
      (node (ref "U8") (pin "7") (pinfunction "~{SHDN}_7") (pintype "input"))
      (node (ref "U9") (pin "4") (pinfunction "VDD_4") (pintype "power_in"))
      (node (ref "U9") (pin "7") (pinfunction "~{SHDN}_7") (pintype "input"))
    )
    (net (code "2") (name "ACCEL_1") (class "Default")
      (node (ref "J5") (pin "5") (pinfunction "5_5") (pintype "passive"))
      (node (ref "U8") (pin "5") (pinfunction "OUT_5") (pintype "output"))
    )
    (net (code "3") (name "ACCEL_1_EXT") (class "Default")
      (node (ref "J5") (pin "3") (pinfunction "3_3") (pintype "passive"))
      (node (ref "U8") (pin "2") (pinfunction "IN_2") (pintype "input"))
    )
    (net (code "4") (name "ACCEL_2") (class "Default")
      (node (ref "J5") (pin "9") (pinfunction "9_9") (pintype "passive"))
      (node (ref "U21") (pin "5") (pinfunction "OUT_5") (pintype "output"))
    )
    (net (code "5") (name "ACCEL_2_EXT") (class "Default")
      (node (ref "J5") (pin "7") (pinfunction "7_7") (pintype "passive"))
      (node (ref "U21") (pin "2") (pinfunction "IN_2") (pintype "input"))
    )
    (net (code "6") (name "BRAKE_1") (class "Default")
      (node (ref "J5") (pin "13") (pinfunction "13_13") (pintype "passive"))
      (node (ref "U19") (pin "5") (pinfunction "OUT_5") (pintype "output"))
    )
    (net (code "7") (name "BRAKE_1_EXT") (class "Default")
      (node (ref "J5") (pin "11") (pinfunction "11_11") (pintype "passive"))
      (node (ref "U19") (pin "2") (pinfunction "IN_2") (pintype "input"))
    )
    (net (code "8") (name "BRAKE_2") (class "Default")
      (node (ref "J5") (pin "17") (pinfunction "17_17") (pintype "passive"))
      (node (ref "U22") (pin "5") (pinfunction "OUT_5") (pintype "output"))
    )
    (net (code "9") (name "BRAKE_2_EXT") (class "Default")
      (node (ref "J5") (pin "15") (pinfunction "15_15") (pintype "passive"))
      (node (ref "U22") (pin "2") (pinfunction "IN_2") (pintype "input"))
    )
    (net (code "10") (name "BRAKE_PRESSURE_F") (class "Default")
      (node (ref "C17") (pin "1") (pinfunction "1_1") (pintype "passive"))
      (node (ref "J5") (pin "28") (pinfunction "28_28") (pintype "passive"))
      (node (ref "R31") (pin "2") (pinfunction "2_2") (pintype "passive"))
    )
    (net (code "11") (name "BRAKE_PRESSURE_F_EXT") (class "Default")
      (node (ref "J5") (pin "27") (pinfunction "27_27") (pintype "passive"))
      (node (ref "R30") (pin "1") (pinfunction "1_1") (pintype "passive"))
    )
    (net (code "12") (name "BRAKE_PRESSURE_R") (class "Default")
      (node (ref "C15") (pin "1") (pinfunction "1_1") (pintype "passive"))
      (node (ref "J5") (pin "30") (pinfunction "30_30") (pintype "passive"))
      (node (ref "R29") (pin "2") (pinfunction "2_2") (pintype "passive"))
    )
    (net (code "13") (name "BRAKE_PRESSURE_R_EXT") (class "Default")
      (node (ref "J5") (pin "29") (pinfunction "29_29") (pintype "passive"))
      (node (ref "R3") (pin "1") (pinfunction "1_1") (pintype "passive"))
    )
    (net (code "14") (name "CURRENT") (class "Default")
      (node (ref "J5") (pin "34") (pinfunction "34_34") (pintype "passive"))
      (node (ref "U11") (pin "5") (pinfunction "OUT_5") (pintype "output"))
    )
    (net (code "15") (name "CURRENT_EXT") (class "Default")
      (node (ref "J5") (pin "32") (pinfunction "32_32") (pintype "passive"))
      (node (ref "R41") (pin "1") (pinfunction "1_1") (pintype "passive"))
    )
    (net (code "16") (name "CURRENT_EXT_5V") (class "Default")
      (node (ref "R41") (pin "2") (pinfunction "2_2") (pintype "passive"))
      (node (ref "R42") (pin "1") (pinfunction "1_1") (pintype "passive"))
      (node (ref "U11") (pin "2") (pinfunction "IN_2") (pintype "input"))
    )
    (net (code "17") (name "GND") (class "Default")
      (node (ref "C1") (pin "2") (pinfunction "2_2") (pintype "passive"))
      (node (ref "C10") (pin "2") (pinfunction "2_2") (pintype "passive"))
      (node (ref "C100") (pin "2") (pinfunction "2_2") (pintype "passive"))
      (node (ref "C101") (pin "2") (pinfunction "2_2") (pintype "passive"))
      (node (ref "C102") (pin "2") (pinfunction "2_2") (pintype "passive"))
      (node (ref "C103") (pin "2") (pinfunction "2_2") (pintype "passive"))
      (node (ref "C104") (pin "2") (pinfunction "2_2") (pintype "passive"))
      (node (ref "C11") (pin "2") (pinfunction "2_2") (pintype "passive"))
      (node (ref "C12") (pin "2") (pinfunction "2_2") (pintype "passive"))
      (node (ref "C13") (pin "2") (pinfunction "2_2") (pintype "passive"))
      (node (ref "C14") (pin "2") (pinfunction "2_2") (pintype "passive"))
      (node (ref "C15") (pin "2") (pinfunction "2_2") (pintype "passive"))
      (node (ref "C16") (pin "2") (pinfunction "2_2") (pintype "passive"))
      (node (ref "C17") (pin "2") (pinfunction "2_2") (pintype "passive"))
      (node (ref "C2") (pin "2") (pinfunction "2_2") (pintype "passive"))
      (node (ref "C25") (pin "2") (pinfunction "2_2") (pintype "passive"))
      (node (ref "C26") (pin "2") (pinfunction "2_2") (pintype "passive"))
      (node (ref "C27") (pin "2") (pinfunction "2_2") (pintype "passive"))
      (node (ref "C28") (pin "2") (pinfunction "2_2") (pintype "passive"))
      (node (ref "C29") (pin "2") (pinfunction "2_2") (pintype "passive"))
      (node (ref "C3") (pin "2") (pinfunction "2_2") (pintype "passive"))
      (node (ref "C30") (pin "2") (pinfunction "2_2") (pintype "passive"))
      (node (ref "C31") (pin "2") (pinfunction "2_2") (pintype "passive"))
      (node (ref "C32") (pin "2") (pinfunction "2_2") (pintype "passive"))
      (node (ref "C33") (pin "2") (pinfunction "2_2") (pintype "passive"))
      (node (ref "C34") (pin "2") (pinfunction "2_2") (pintype "passive"))
      (node (ref "C35") (pin "2") (pinfunction "2_2") (pintype "passive"))
      (node (ref "C36") (pin "2") (pinfunction "2_2") (pintype "passive"))
      (node (ref "C37") (pin "2") (pinfunction "2_2") (pintype "passive"))
      (node (ref "C38") (pin "2") (pinfunction "2_2") (pintype "passive"))
      (node (ref "C39") (pin "2") (pinfunction "2_2") (pintype "passive"))
      (node (ref "C4") (pin "2") (pinfunction "2_2") (pintype "passive"))
      (node (ref "C40") (pin "2") (pinfunction "2_2") (pintype "passive"))
      (node (ref "C41") (pin "2") (pinfunction "2_2") (pintype "passive"))
      (node (ref "C42") (pin "2") (pinfunction "2_2") (pintype "passive"))
      (node (ref "C43") (pin "2") (pinfunction "2_2") (pintype "passive"))
      (node (ref "C44") (pin "2") (pinfunction "2_2") (pintype "passive"))
      (node (ref "C45") (pin "2") (pinfunction "2_2") (pintype "passive"))
      (node (ref "C46") (pin "2") (pinfunction "2_2") (pintype "passive"))
      (node (ref "C47") (pin "2") (pinfunction "2_2") (pintype "passive"))
      (node (ref "C48") (pin "2") (pinfunction "2_2") (pintype "passive"))
      (node (ref "C5") (pin "2") (pinfunction "2_2") (pintype "passive"))
      (node (ref "C7") (pin "2") (pinfunction "2_2") (pintype "passive"))
      (node (ref "C8") (pin "2") (pinfunction "2_2") (pintype "passive"))
      (node (ref "C81") (pin "2") (pinfunction "2_2") (pintype "passive"))
      (node (ref "C82") (pin "2") (pinfunction "2_2") (pintype "passive"))
      (node (ref "C83") (pin "2") (pinfunction "2_2") (pintype "passive"))
      (node (ref "C84") (pin "2") (pinfunction "2_2") (pintype "passive"))
      (node (ref "C85") (pin "2") (pinfunction "2_2") (pintype "passive"))
      (node (ref "C86") (pin "2") (pinfunction "2_2") (pintype "passive"))
      (node (ref "C87") (pin "2") (pinfunction "2_2") (pintype "passive"))
      (node (ref "C88") (pin "2") (pinfunction "2_2") (pintype "passive"))
      (node (ref "C89") (pin "2") (pinfunction "2_2") (pintype "passive"))
      (node (ref "C9") (pin "2") (pinfunction "2_2") (pintype "passive"))
      (node (ref "C90") (pin "2") (pinfunction "2_2") (pintype "passive"))
      (node (ref "C91") (pin "2") (pinfunction "2_2") (pintype "passive"))
      (node (ref "C92") (pin "2") (pinfunction "2_2") (pintype "passive"))
      (node (ref "C93") (pin "2") (pinfunction "2_2") (pintype "passive"))
      (node (ref "C94") (pin "2") (pinfunction "2_2") (pintype "passive"))
      (node (ref "C95") (pin "2") (pinfunction "2_2") (pintype "passive"))
      (node (ref "C96") (pin "2") (pinfunction "2_2") (pintype "passive"))
      (node (ref "C97") (pin "2") (pinfunction "2_2") (pintype "passive"))
      (node (ref "C98") (pin "2") (pinfunction "2_2") (pintype "passive"))
      (node (ref "C99") (pin "2") (pinfunction "2_2") (pintype "passive"))
      (node (ref "J4") (pin "10") (pinfunction "10_10") (pintype "passive"))
      (node (ref "J4") (pin "12") (pinfunction "12_12") (pintype "passive"))
      (node (ref "J4") (pin "14") (pinfunction "14_14") (pintype "passive"))
      (node (ref "J4") (pin "16") (pinfunction "16_16") (pintype "passive"))
      (node (ref "J4") (pin "18") (pinfunction "18_18") (pintype "passive"))
      (node (ref "J4") (pin "2") (pinfunction "2_2") (pintype "passive"))
      (node (ref "J4") (pin "20") (pinfunction "20_20") (pintype "passive"))
      (node (ref "J4") (pin "22") (pinfunction "22_22") (pintype "passive"))
      (node (ref "J4") (pin "24") (pinfunction "24_24") (pintype "passive"))
      (node (ref "J4") (pin "26") (pinfunction "26_26") (pintype "passive"))
      (node (ref "J4") (pin "28") (pinfunction "28_28") (pintype "passive"))
      (node (ref "J4") (pin "30") (pinfunction "30_30") (pintype "passive"))
      (node (ref "J4") (pin "32") (pinfunction "32_32") (pintype "passive"))
      (node (ref "J4") (pin "34") (pinfunction "34_34") (pintype "passive"))
      (node (ref "J4") (pin "36") (pinfunction "36_36") (pintype "passive"))
      (node (ref "J4") (pin "38") (pinfunction "38_38") (pintype "passive"))
      (node (ref "J4") (pin "4") (pinfunction "4_4") (pintype "passive"))
      (node (ref "J4") (pin "6") (pinfunction "6_6") (pintype "passive"))
      (node (ref "J4") (pin "8") (pinfunction "8_8") (pintype "passive"))
      (node (ref "J5") (pin "10") (pinfunction "10_10") (pintype "passive"))
      (node (ref "J5") (pin "12") (pinfunction "12_12") (pintype "passive"))
      (node (ref "J5") (pin "14") (pinfunction "14_14") (pintype "passive"))
      (node (ref "J5") (pin "16") (pinfunction "16_16") (pintype "passive"))
      (node (ref "J5") (pin "18") (pinfunction "18_18") (pintype "passive"))
      (node (ref "J5") (pin "2") (pinfunction "2_2") (pintype "passive"))
      (node (ref "J5") (pin "20") (pinfunction "20_20") (pintype "passive"))
      (node (ref "J5") (pin "22") (pinfunction "22_22") (pintype "passive"))
      (node (ref "J5") (pin "24") (pinfunction "24_24") (pintype "passive"))
      (node (ref "J5") (pin "26") (pinfunction "26_26") (pintype "passive"))
      (node (ref "J5") (pin "31") (pinfunction "31_31") (pintype "passive"))
      (node (ref "J5") (pin "33") (pinfunction "33_33") (pintype "passive"))
      (node (ref "J5") (pin "35") (pinfunction "35_35") (pintype "passive"))
      (node (ref "J5") (pin "37") (pinfunction "37_37") (pintype "passive"))
      (node (ref "J5") (pin "4") (pinfunction "4_4") (pintype "passive"))
      (node (ref "J5") (pin "6") (pinfunction "6_6") (pintype "passive"))
      (node (ref "J5") (pin "8") (pinfunction "8_8") (pintype "passive"))
      (node (ref "R10") (pin "2") (pinfunction "2_2") (pintype "passive"))
      (node (ref "R12") (pin "2") (pinfunction "2_2") (pintype "passive"))
      (node (ref "R16") (pin "2") (pinfunction "2_2") (pintype "passive"))
      (node (ref "R18") (pin "2") (pinfunction "2_2") (pintype "passive"))
      (node (ref "R24") (pin "2") (pinfunction "2_2") (pintype "passive"))
      (node (ref "R28") (pin "2") (pinfunction "2_2") (pintype "passive"))
      (node (ref "R36") (pin "2") (pinfunction "2_2") (pintype "passive"))
      (node (ref "R38") (pin "2") (pinfunction "2_2") (pintype "passive"))
      (node (ref "R40") (pin "2") (pinfunction "2_2") (pintype "passive"))
      (node (ref "R42") (pin "2") (pinfunction "2_2") (pintype "passive"))
      (node (ref "R44") (pin "2") (pinfunction "2_2") (pintype "passive"))
      (node (ref "R6") (pin "2") (pinfunction "2_2") (pintype "passive"))
      (node (ref "U10") (pin "3") (pinfunction "GND_3") (pintype "power_in"))
      (node (ref "U11") (pin "3") (pinfunction "GND_3") (pintype "power_in"))
      (node (ref "U19") (pin "3") (pinfunction "GND_3") (pintype "power_in"))
      (node (ref "U20") (pin "3") (pinfunction "GND_3") (pintype "power_in"))
      (node (ref "U21") (pin "3") (pinfunction "GND_3") (pintype "power_in"))
      (node (ref "U22") (pin "3") (pinfunction "GND_3") (pintype "power_in"))
      (node (ref "U23") (pin "3") (pinfunction "GND_3") (pintype "power_in"))
      (node (ref "U24") (pin "3") (pinfunction "GND_3") (pintype "power_in"))
      (node (ref "U6") (pin "3") (pinfunction "GND_3") (pintype "power_in"))
      (node (ref "U7") (pin "3") (pinfunction "GND_3") (pintype "power_in"))
      (node (ref "U8") (pin "3") (pinfunction "GND_3") (pintype "power_in"))
      (node (ref "U9") (pin "3") (pinfunction "GND_3") (pintype "power_in"))
    )
    (net (code "18") (name "LOAD_FL") (class "Default")
      (node (ref "J4") (pin "5") (pinfunction "5_5") (pintype "passive"))
      (node (ref "U9") (pin "5") (pinfunction "OUT_5") (pintype "output"))
    )
    (net (code "19") (name "LOAD_FL_EXT") (class "Default")
      (node (ref "J4") (pin "3") (pinfunction "3_3") (pintype "passive"))
      (node (ref "R37") (pin "1") (pinfunction "1_1") (pintype "passive"))
    )
    (net (code "20") (name "LOAD_FL_EXT_5V") (class "Default")
      (node (ref "R37") (pin "2") (pinfunction "2_2") (pintype "passive"))
      (node (ref "R38") (pin "1") (pinfunction "1_1") (pintype "passive"))
      (node (ref "U9") (pin "2") (pinfunction "IN_2") (pintype "input"))
    )
    (net (code "21") (name "LOAD_FR") (class "Default")
      (node (ref "J4") (pin "9") (pinfunction "9_9") (pintype "passive"))
      (node (ref "U10") (pin "5") (pinfunction "OUT_5") (pintype "output"))
    )
    (net (code "22") (name "LOAD_FR_EXT") (class "Default")
      (node (ref "J4") (pin "7") (pinfunction "7_7") (pintype "passive"))
      (node (ref "R39") (pin "1") (pinfunction "1_1") (pintype "passive"))
    )
    (net (code "23") (name "LOAD_FR_EXT_5V") (class "Default")
      (node (ref "R39") (pin "2") (pinfunction "2_2") (pintype "passive"))
      (node (ref "R40") (pin "1") (pinfunction "1_1") (pintype "passive"))
      (node (ref "U10") (pin "2") (pinfunction "IN_2") (pintype "input"))
    )
    (net (code "24") (name "LOAD_RL") (class "Default")
      (node (ref "J4") (pin "13") (pinfunction "13_13") (pintype "passive"))
      (node (ref "U6") (pin "5") (pinfunction "OUT_5") (pintype "output"))
    )
    (net (code "25") (name "LOAD_RL_EXT") (class "Default")
      (node (ref "J4") (pin "11") (pinfunction "11_11") (pintype "passive"))
      (node (ref "R27") (pin "1") (pinfunction "1_1") (pintype "passive"))
    )
    (net (code "26") (name "LOAD_RL_EXT_5V") (class "Default")
      (node (ref "R27") (pin "2") (pinfunction "2_2") (pintype "passive"))
      (node (ref "R28") (pin "1") (pinfunction "1_1") (pintype "passive"))
      (node (ref "U6") (pin "2") (pinfunction "IN_2") (pintype "input"))
    )
    (net (code "27") (name "LOAD_RR") (class "Default")
      (node (ref "J4") (pin "17") (pinfunction "17_17") (pintype "passive"))
      (node (ref "U7") (pin "5") (pinfunction "OUT_5") (pintype "output"))
    )
    (net (code "28") (name "LOAD_RR_EXT") (class "Default")
      (node (ref "J4") (pin "15") (pinfunction "15_15") (pintype "passive"))
      (node (ref "R35") (pin "1") (pinfunction "1_1") (pintype "passive"))
    )
    (net (code "29") (name "LOAD_RR_EXT_5V") (class "Default")
      (node (ref "R35") (pin "2") (pinfunction "2_2") (pintype "passive"))
      (node (ref "R36") (pin "1") (pinfunction "1_1") (pintype "passive"))
      (node (ref "U7") (pin "2") (pinfunction "IN_2") (pintype "input"))
    )
    (net (code "30") (name "Net-(C1-Pad1)") (class "Default")
      (node (ref "C1") (pin "1") (pinfunction "1_1") (pintype "passive"))
      (node (ref "R7") (pin "2") (pinfunction "2_2") (pintype "passive"))
      (node (ref "R8") (pin "1") (pinfunction "1_1") (pintype "passive"))
    )
    (net (code "31") (name "Net-(C2-Pad1)") (class "Default")
      (node (ref "C2") (pin "1") (pinfunction "1_1") (pintype "passive"))
      (node (ref "R29") (pin "1") (pinfunction "1_1") (pintype "passive"))
      (node (ref "R3") (pin "2") (pinfunction "2_2") (pintype "passive"))
    )
    (net (code "32") (name "Net-(C3-Pad1)") (class "Default")
      (node (ref "C3") (pin "1") (pinfunction "1_1") (pintype "passive"))
      (node (ref "R1") (pin "2") (pinfunction "2_2") (pintype "passive"))
      (node (ref "R5") (pin "1") (pinfunction "1_1") (pintype "passive"))
    )
    (net (code "33") (name "Net-(C4-Pad1)") (class "Default")
      (node (ref "C4") (pin "1") (pinfunction "1_1") (pintype "passive"))
      (node (ref "R13") (pin "2") (pinfunction "2_2") (pintype "passive"))
      (node (ref "R14") (pin "1") (pinfunction "1_1") (pintype "passive"))
    )
    (net (code "34") (name "Net-(C7-Pad1)") (class "Default")
      (node (ref "C7") (pin "1") (pinfunction "1_1") (pintype "passive"))
      (node (ref "R21") (pin "2") (pinfunction "2_2") (pintype "passive"))
      (node (ref "R22") (pin "1") (pinfunction "1_1") (pintype "passive"))
    )
    (net (code "35") (name "Net-(C10-Pad1)") (class "Default")
      (node (ref "C10") (pin "1") (pinfunction "1_1") (pintype "passive"))
      (node (ref "R19") (pin "2") (pinfunction "2_2") (pintype "passive"))
      (node (ref "R20") (pin "1") (pinfunction "1_1") (pintype "passive"))
    )
    (net (code "36") (name "Net-(C13-Pad1)") (class "Default")
      (node (ref "C13") (pin "1") (pinfunction "1_1") (pintype "passive"))
      (node (ref "R25") (pin "2") (pinfunction "2_2") (pintype "passive"))
      (node (ref "R26") (pin "1") (pinfunction "1_1") (pintype "passive"))
    )
    (net (code "37") (name "Net-(C16-Pad1)") (class "Default")
      (node (ref "C16") (pin "1") (pinfunction "1_1") (pintype "passive"))
      (node (ref "R30") (pin "2") (pinfunction "2_2") (pintype "passive"))
      (node (ref "R31") (pin "1") (pinfunction "1_1") (pintype "passive"))
    )
    (net (code "38") (name "Net-(R1-Pad1)") (class "Default")
      (node (ref "R1") (pin "1") (pinfunction "1_1") (pintype "passive"))
      (node (ref "R10") (pin "1") (pinfunction "1_1") (pintype "passive"))
      (node (ref "R9") (pin "2") (pinfunction "2_2") (pintype "passive"))
    )
    (net (code "39") (name "Net-(R4-Pad2)") (class "Default")
      (node (ref "R4") (pin "2") (pinfunction "2_2") (pintype "passive"))
      (node (ref "R6") (pin "1") (pinfunction "1_1") (pintype "passive"))
      (node (ref "R7") (pin "1") (pinfunction "1_1") (pintype "passive"))
    )
    (net (code "40") (name "Net-(R11-Pad2)") (class "Default")
      (node (ref "R11") (pin "2") (pinfunction "2_2") (pintype "passive"))
      (node (ref "R12") (pin "1") (pinfunction "1_1") (pintype "passive"))
      (node (ref "R13") (pin "1") (pinfunction "1_1") (pintype "passive"))
    )
    (net (code "41") (name "Net-(R15-Pad2)") (class "Default")
      (node (ref "R15") (pin "2") (pinfunction "2_2") (pintype "passive"))
      (node (ref "R16") (pin "1") (pinfunction "1_1") (pintype "passive"))
      (node (ref "R19") (pin "1") (pinfunction "1_1") (pintype "passive"))
    )
    (net (code "42") (name "Net-(R17-Pad2)") (class "Default")
      (node (ref "R17") (pin "2") (pinfunction "2_2") (pintype "passive"))
      (node (ref "R18") (pin "1") (pinfunction "1_1") (pintype "passive"))
      (node (ref "R21") (pin "1") (pinfunction "1_1") (pintype "passive"))
    )
    (net (code "43") (name "Net-(R23-Pad2)") (class "Default")
      (node (ref "R23") (pin "2") (pinfunction "2_2") (pintype "passive"))
      (node (ref "R24") (pin "1") (pinfunction "1_1") (pintype "passive"))
      (node (ref "R25") (pin "1") (pinfunction "1_1") (pintype "passive"))
    )
    (net (code "44") (name "Net-(U6-CLK)") (class "Default")
      (node (ref "C28") (pin "1") (pinfunction "1_1") (pintype "passive"))
      (node (ref "U6") (pin "8") (pinfunction "CLK_8") (pintype "input"))
    )
    (net (code "45") (name "Net-(U6-COM)") (class "Default")
      (node (ref "C27") (pin "1") (pinfunction "1_1") (pintype "passive"))
      (node (ref "U6") (pin "1") (pinfunction "COM_1") (pintype "bidirectional"))
      (node (ref "U6") (pin "6") (pinfunction "OS_6") (pintype "bidirectional"))
    )
    (net (code "46") (name "Net-(U7-CLK)") (class "Default")
      (node (ref "C32") (pin "1") (pinfunction "1_1") (pintype "passive"))
      (node (ref "U7") (pin "8") (pinfunction "CLK_8") (pintype "input"))
    )
    (net (code "47") (name "Net-(U7-COM)") (class "Default")
      (node (ref "C31") (pin "1") (pinfunction "1_1") (pintype "passive"))
      (node (ref "U7") (pin "1") (pinfunction "COM_1") (pintype "bidirectional"))
      (node (ref "U7") (pin "6") (pinfunction "OS_6") (pintype "bidirectional"))
    )
    (net (code "48") (name "Net-(U8-CLK)") (class "Default")
      (node (ref "C36") (pin "1") (pinfunction "1_1") (pintype "passive"))
      (node (ref "U8") (pin "8") (pinfunction "CLK_8") (pintype "input"))
    )
    (net (code "49") (name "Net-(U8-COM)") (class "Default")
      (node (ref "C35") (pin "1") (pinfunction "1_1") (pintype "passive"))
      (node (ref "U8") (pin "1") (pinfunction "COM_1") (pintype "bidirectional"))
      (node (ref "U8") (pin "6") (pinfunction "OS_6") (pintype "bidirectional"))
    )
    (net (code "50") (name "Net-(U9-CLK)") (class "Default")
      (node (ref "C40") (pin "1") (pinfunction "1_1") (pintype "passive"))
      (node (ref "U9") (pin "8") (pinfunction "CLK_8") (pintype "input"))
    )
    (net (code "51") (name "Net-(U9-COM)") (class "Default")
      (node (ref "C39") (pin "1") (pinfunction "1_1") (pintype "passive"))
      (node (ref "U9") (pin "1") (pinfunction "COM_1") (pintype "bidirectional"))
      (node (ref "U9") (pin "6") (pinfunction "OS_6") (pintype "bidirectional"))
    )
    (net (code "52") (name "Net-(U10-CLK)") (class "Default")
      (node (ref "C44") (pin "1") (pinfunction "1_1") (pintype "passive"))
      (node (ref "U10") (pin "8") (pinfunction "CLK_8") (pintype "input"))
    )
    (net (code "53") (name "Net-(U10-COM)") (class "Default")
      (node (ref "C43") (pin "1") (pinfunction "1_1") (pintype "passive"))
      (node (ref "U10") (pin "1") (pinfunction "COM_1") (pintype "bidirectional"))
      (node (ref "U10") (pin "6") (pinfunction "OS_6") (pintype "bidirectional"))
    )
    (net (code "54") (name "Net-(U11-CLK)") (class "Default")
      (node (ref "C48") (pin "1") (pinfunction "1_1") (pintype "passive"))
      (node (ref "U11") (pin "8") (pinfunction "CLK_8") (pintype "input"))
    )
    (net (code "55") (name "Net-(U11-COM)") (class "Default")
      (node (ref "C47") (pin "1") (pinfunction "1_1") (pintype "passive"))
      (node (ref "U11") (pin "1") (pinfunction "COM_1") (pintype "bidirectional"))
      (node (ref "U11") (pin "6") (pinfunction "OS_6") (pintype "bidirectional"))
    )
    (net (code "56") (name "Net-(U19-CLK)") (class "Default")
      (node (ref "C84") (pin "1") (pinfunction "1_1") (pintype "passive"))
      (node (ref "U19") (pin "8") (pinfunction "CLK_8") (pintype "input"))
    )
    (net (code "57") (name "Net-(U19-COM)") (class "Default")
      (node (ref "C83") (pin "1") (pinfunction "1_1") (pintype "passive"))
      (node (ref "U19") (pin "1") (pinfunction "COM_1") (pintype "bidirectional"))
      (node (ref "U19") (pin "6") (pinfunction "OS_6") (pintype "bidirectional"))
    )
    (net (code "58") (name "Net-(U20-CLK)") (class "Default")
      (node (ref "C88") (pin "1") (pinfunction "1_1") (pintype "passive"))
      (node (ref "U20") (pin "8") (pinfunction "CLK_8") (pintype "input"))
    )
    (net (code "59") (name "Net-(U20-COM)") (class "Default")
      (node (ref "C87") (pin "1") (pinfunction "1_1") (pintype "passive"))
      (node (ref "U20") (pin "1") (pinfunction "COM_1") (pintype "bidirectional"))
      (node (ref "U20") (pin "6") (pinfunction "OS_6") (pintype "bidirectional"))
    )
    (net (code "60") (name "Net-(U21-CLK)") (class "Default")
      (node (ref "C92") (pin "1") (pinfunction "1_1") (pintype "passive"))
      (node (ref "U21") (pin "8") (pinfunction "CLK_8") (pintype "input"))
    )
    (net (code "61") (name "Net-(U21-COM)") (class "Default")
      (node (ref "C91") (pin "1") (pinfunction "1_1") (pintype "passive"))
      (node (ref "U21") (pin "1") (pinfunction "COM_1") (pintype "bidirectional"))
      (node (ref "U21") (pin "6") (pinfunction "OS_6") (pintype "bidirectional"))
    )
    (net (code "62") (name "Net-(U22-CLK)") (class "Default")
      (node (ref "C96") (pin "1") (pinfunction "1_1") (pintype "passive"))
      (node (ref "U22") (pin "8") (pinfunction "CLK_8") (pintype "input"))
    )
    (net (code "63") (name "Net-(U22-COM)") (class "Default")
      (node (ref "C95") (pin "1") (pinfunction "1_1") (pintype "passive"))
      (node (ref "U22") (pin "1") (pinfunction "COM_1") (pintype "bidirectional"))
      (node (ref "U22") (pin "6") (pinfunction "OS_6") (pintype "bidirectional"))
    )
    (net (code "64") (name "Net-(U23-CLK)") (class "Default")
      (node (ref "C100") (pin "1") (pinfunction "1_1") (pintype "passive"))
      (node (ref "U23") (pin "8") (pinfunction "CLK_8") (pintype "input"))
    )
    (net (code "65") (name "Net-(U23-COM)") (class "Default")
      (node (ref "C99") (pin "1") (pinfunction "1_1") (pintype "passive"))
      (node (ref "U23") (pin "1") (pinfunction "COM_1") (pintype "bidirectional"))
      (node (ref "U23") (pin "6") (pinfunction "OS_6") (pintype "bidirectional"))
    )
    (net (code "66") (name "Net-(U24-CLK)") (class "Default")
      (node (ref "C104") (pin "1") (pinfunction "1_1") (pintype "passive"))
      (node (ref "U24") (pin "8") (pinfunction "CLK_8") (pintype "input"))
    )
    (net (code "67") (name "Net-(U24-COM)") (class "Default")
      (node (ref "C103") (pin "1") (pinfunction "1_1") (pintype "passive"))
      (node (ref "U24") (pin "1") (pinfunction "COM_1") (pintype "bidirectional"))
      (node (ref "U24") (pin "6") (pinfunction "OS_6") (pintype "bidirectional"))
    )
    (net (code "68") (name "REFERENCE") (class "Default")
      (node (ref "J5") (pin "38") (pinfunction "38_38") (pintype "passive"))
      (node (ref "U24") (pin "5") (pinfunction "OUT_5") (pintype "output"))
    )
    (net (code "69") (name "REFERENCE_EXT") (class "Default")
      (node (ref "J5") (pin "36") (pinfunction "36_36") (pintype "passive"))
      (node (ref "R43") (pin "1") (pinfunction "1_1") (pintype "passive"))
    )
    (net (code "70") (name "REFERENCE_EXT_5V") (class "Default")
      (node (ref "R43") (pin "2") (pinfunction "2_2") (pintype "passive"))
      (node (ref "R44") (pin "1") (pinfunction "1_1") (pintype "passive"))
      (node (ref "U24") (pin "2") (pinfunction "IN_2") (pintype "input"))
    )
    (net (code "71") (name "SPN_POT_1") (class "Default")
      (node (ref "C9") (pin "1") (pinfunction "1_1") (pintype "passive"))
      (node (ref "J4") (pin "21") (pinfunction "21_21") (pintype "passive"))
      (node (ref "R5") (pin "2") (pinfunction "2_2") (pintype "passive"))
    )
    (net (code "72") (name "SPN_POT_1_EXT") (class "Default")
      (node (ref "J4") (pin "19") (pinfunction "19_19") (pintype "passive"))
      (node (ref "R9") (pin "1") (pinfunction "1_1") (pintype "passive"))
    )
    (net (code "73") (name "SPN_POT_2") (class "Default")
      (node (ref "C8") (pin "1") (pinfunction "1_1") (pintype "passive"))
      (node (ref "J4") (pin "25") (pinfunction "25_25") (pintype "passive"))
      (node (ref "R8") (pin "2") (pinfunction "2_2") (pintype "passive"))
    )
    (net (code "74") (name "SPN_POT_2_EXT") (class "Default")
      (node (ref "J4") (pin "23") (pinfunction "23_23") (pintype "passive"))
      (node (ref "R4") (pin "1") (pinfunction "1_1") (pintype "passive"))
    )
    (net (code "75") (name "SPN_POT_3") (class "Default")
      (node (ref "C11") (pin "1") (pinfunction "1_1") (pintype "passive"))
      (node (ref "J4") (pin "29") (pinfunction "29_29") (pintype "passive"))
      (node (ref "R20") (pin "2") (pinfunction "2_2") (pintype "passive"))
    )
    (net (code "76") (name "SPN_POT_3_EXT") (class "Default")
      (node (ref "J4") (pin "27") (pinfunction "27_27") (pintype "passive"))
      (node (ref "R15") (pin "1") (pinfunction "1_1") (pintype "passive"))
    )
    (net (code "77") (name "SPN_POT_4") (class "Default")
      (node (ref "C5") (pin "1") (pinfunction "1_1") (pintype "passive"))
      (node (ref "J4") (pin "33") (pinfunction "33_33") (pintype "passive"))
      (node (ref "R14") (pin "2") (pinfunction "2_2") (pintype "passive"))
    )
    (net (code "78") (name "SPN_POT_4_EXT") (class "Default")
      (node (ref "J4") (pin "31") (pinfunction "31_31") (pintype "passive"))
      (node (ref "R11") (pin "1") (pinfunction "1_1") (pintype "passive"))
    )
    (net (code "79") (name "SPN_POT_5") (class "Default")
      (node (ref "C12") (pin "1") (pinfunction "1_1") (pintype "passive"))
      (node (ref "J4") (pin "37") (pinfunction "37_37") (pintype "passive"))
      (node (ref "R22") (pin "2") (pinfunction "2_2") (pintype "passive"))
    )
    (net (code "80") (name "SPN_POT_5_EXT") (class "Default")
      (node (ref "J4") (pin "35") (pinfunction "35_35") (pintype "passive"))
      (node (ref "R17") (pin "1") (pinfunction "1_1") (pintype "passive"))
    )
    (net (code "81") (name "SPN_POT_6") (class "Default")
      (node (ref "C14") (pin "1") (pinfunction "1_1") (pintype "passive"))
      (node (ref "J5") (pin "1") (pinfunction "1_1") (pintype "passive"))
      (node (ref "R26") (pin "2") (pinfunction "2_2") (pintype "passive"))
    )
    (net (code "82") (name "SPN_POT_6_EXT") (class "Default")
      (node (ref "J4") (pin "39") (pinfunction "39_39") (pintype "passive"))
      (node (ref "R23") (pin "1") (pinfunction "1_1") (pintype "passive"))
    )
    (net (code "83") (name "STEERING_1") (class "Default")
      (node (ref "J5") (pin "21") (pinfunction "21_21") (pintype "passive"))
      (node (ref "U20") (pin "5") (pinfunction "OUT_5") (pintype "output"))
    )
    (net (code "84") (name "STEERING_1_EXT") (class "Default")
      (node (ref "J5") (pin "19") (pinfunction "19_19") (pintype "passive"))
      (node (ref "U20") (pin "2") (pinfunction "IN_2") (pintype "input"))
    )
    (net (code "85") (name "STEERING_2") (class "Default")
      (node (ref "J5") (pin "25") (pinfunction "25_25") (pintype "passive"))
      (node (ref "U23") (pin "5") (pinfunction "OUT_5") (pintype "output"))
    )
    (net (code "86") (name "STEERING_2_EXT") (class "Default")
      (node (ref "J5") (pin "23") (pinfunction "23_23") (pintype "passive"))
      (node (ref "U23") (pin "2") (pinfunction "IN_2") (pintype "input"))
    )
    (net (code "87") (name "unconnected-(J4-Pad40)") (class "Default")
      (node (ref "J4") (pin "40") (pinfunction "40_40") (pintype "passive"))
    )
    (net (code "88") (name "unconnected-(J5-Pad39)") (class "Default")
      (node (ref "J5") (pin "39") (pinfunction "39_39") (pintype "passive"))
    )
    (net (code "89") (name "unconnected-(J5-Pad40)") (class "Default")
      (node (ref "J5") (pin "40") (pinfunction "40_40") (pintype "passive"))
    )
  )
)
